# Fenyjelzo.net
KiCad netlist of a schematic drawn in EAGLE
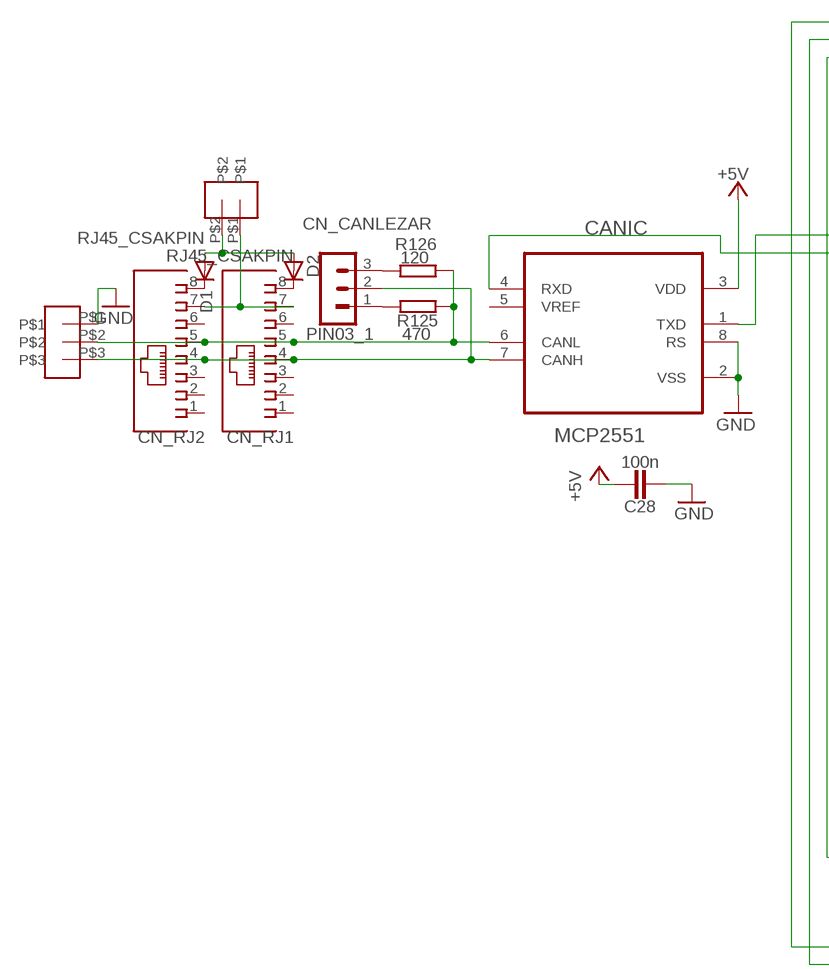
[diagram p0: schematic, sheet 1, part 1 of 2]
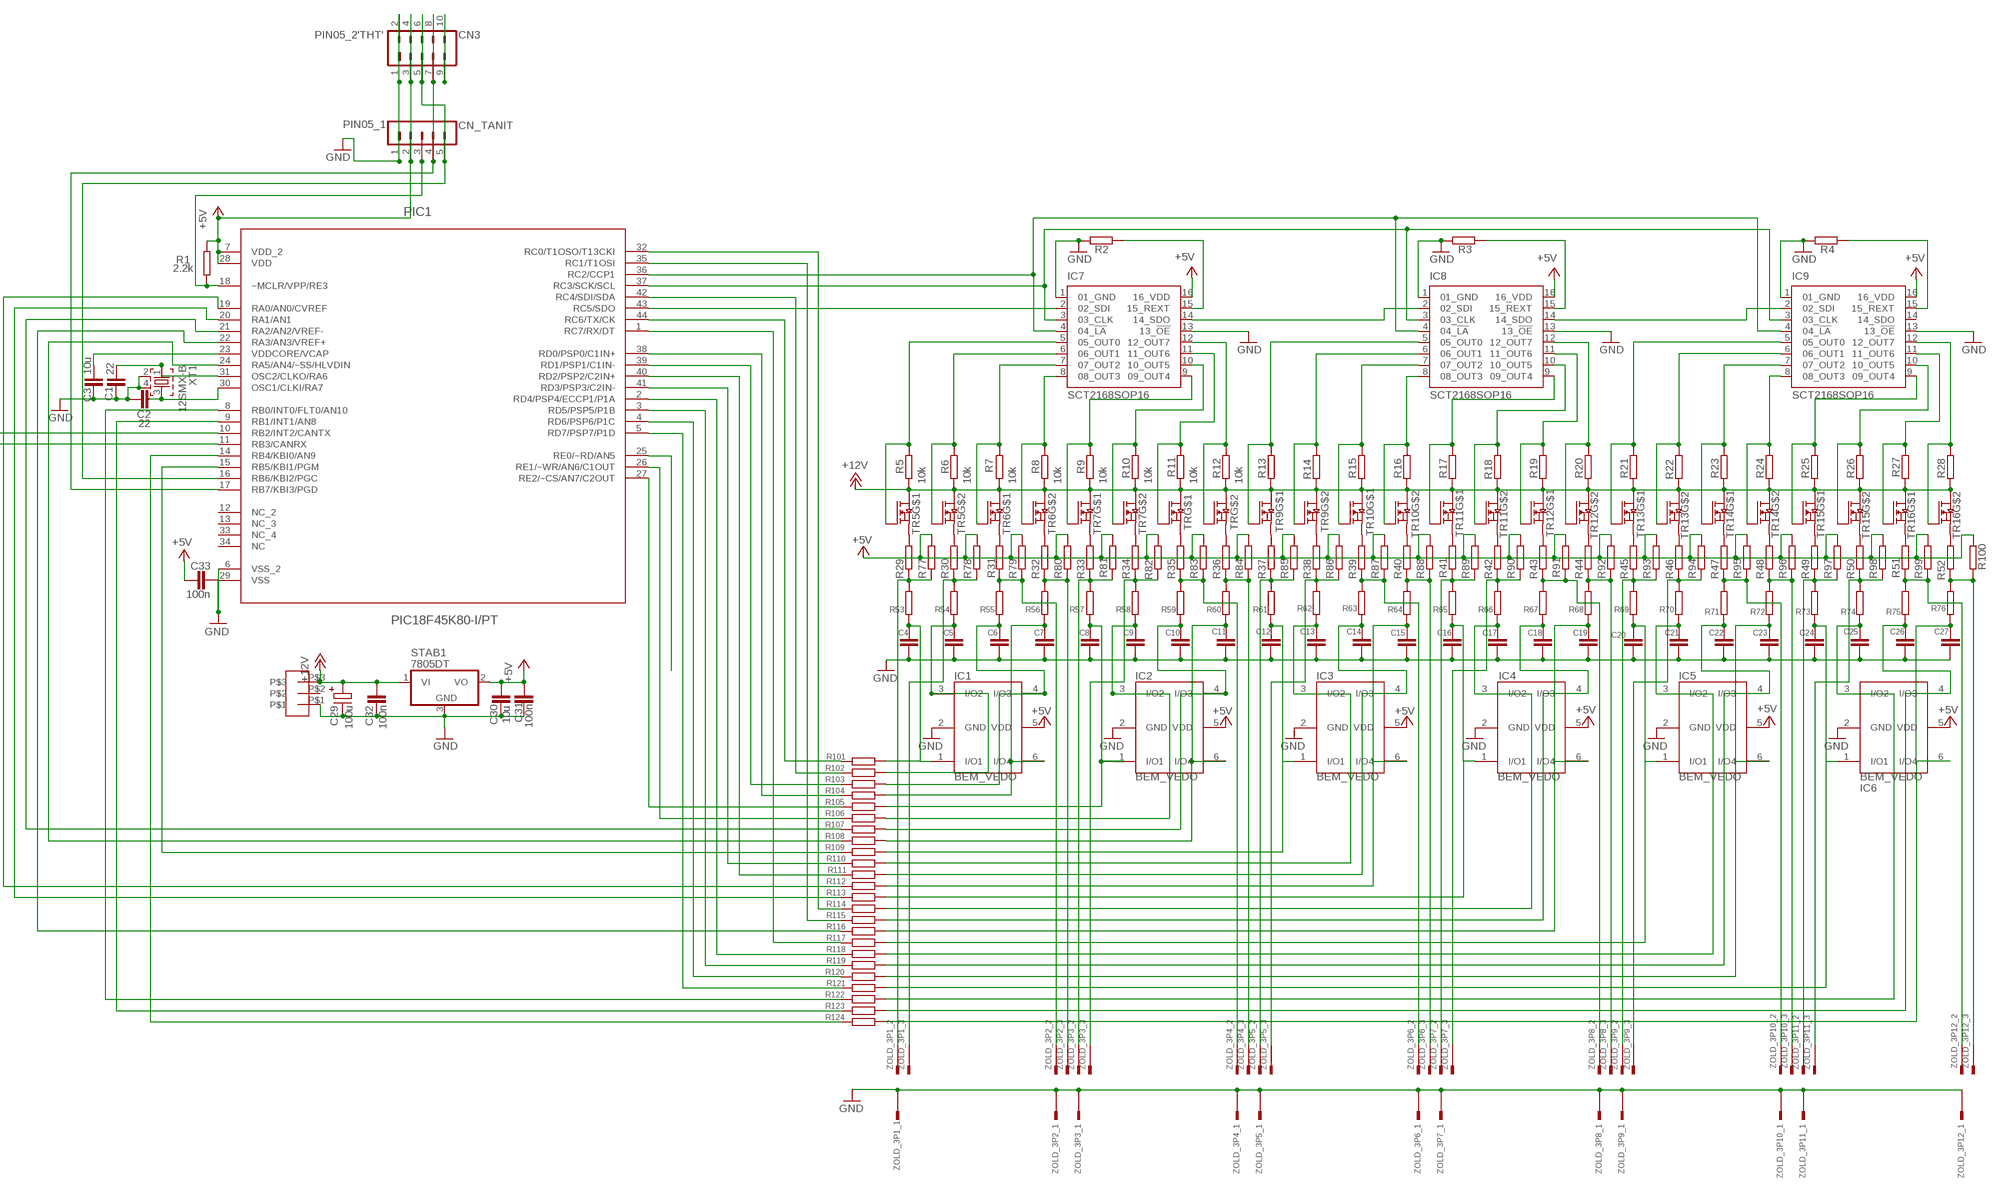
[diagram p1: schematic, sheet 1, part 2 of 2]

(export (version "E")
  (design (tool "Eeschema 10.0.6"))
  (components
    (comp (ref "C1")
      (value "22")
      (footprint "eagle-import:R0805")
      (libsource (lib "eagle-import") (part "C0805"))
    )
    (comp (ref "C2")
      (value "22")
      (footprint "eagle-import:R0805")
      (libsource (lib "eagle-import") (part "C0805"))
    )
    (comp (ref "C3")
      (value "10u")
      (footprint "eagle-import:R0805")
      (libsource (lib "eagle-import") (part "C0805"))
    )
    (comp (ref "C4")
      (value "C0805")
      (footprint "eagle-import:R0805")
      (libsource (lib "eagle-import") (part "C0805"))
    )
    (comp (ref "C5")
      (value "C0805")
      (footprint "eagle-import:R0805")
      (libsource (lib "eagle-import") (part "C0805"))
    )
    (comp (ref "C6")
      (value "C0805")
      (footprint "eagle-import:R0805")
      (libsource (lib "eagle-import") (part "C0805"))
    )
    (comp (ref "C7")
      (value "C0805")
      (footprint "eagle-import:R0805")
      (libsource (lib "eagle-import") (part "C0805"))
    )
    (comp (ref "C8")
      (value "C0805")
      (footprint "eagle-import:R0805")
      (libsource (lib "eagle-import") (part "C0805"))
    )
    (comp (ref "C9")
      (value "C0805")
      (footprint "eagle-import:R0805")
      (libsource (lib "eagle-import") (part "C0805"))
    )
    (comp (ref "C10")
      (value "C0805")
      (footprint "eagle-import:R0805")
      (libsource (lib "eagle-import") (part "C0805"))
    )
    (comp (ref "C11")
      (value "C0805")
      (footprint "eagle-import:R0805")
      (libsource (lib "eagle-import") (part "C0805"))
    )
    (comp (ref "C12")
      (value "C0805")
      (footprint "eagle-import:R0805")
      (libsource (lib "eagle-import") (part "C0805"))
    )
    (comp (ref "C13")
      (value "C0805")
      (footprint "eagle-import:R0805")
      (libsource (lib "eagle-import") (part "C0805"))
    )
    (comp (ref "C14")
      (value "C0805")
      (footprint "eagle-import:R0805")
      (libsource (lib "eagle-import") (part "C0805"))
    )
    (comp (ref "C15")
      (value "C0805")
      (footprint "eagle-import:R0805")
      (libsource (lib "eagle-import") (part "C0805"))
    )
    (comp (ref "C16")
      (value "C0805")
      (footprint "eagle-import:R0805")
      (libsource (lib "eagle-import") (part "C0805"))
    )
    (comp (ref "C17")
      (value "C0805")
      (footprint "eagle-import:R0805")
      (libsource (lib "eagle-import") (part "C0805"))
    )
    (comp (ref "C18")
      (value "C0805")
      (footprint "eagle-import:R0805")
      (libsource (lib "eagle-import") (part "C0805"))
    )
    (comp (ref "C19")
      (value "C0805")
      (footprint "eagle-import:R0805")
      (libsource (lib "eagle-import") (part "C0805"))
    )
    (comp (ref "C20")
      (value "C0805")
      (footprint "eagle-import:R0805")
      (libsource (lib "eagle-import") (part "C0805"))
    )
    (comp (ref "C21")
      (value "C0805")
      (footprint "eagle-import:R0805")
      (libsource (lib "eagle-import") (part "C0805"))
    )
    (comp (ref "C22")
      (value "C0805")
      (footprint "eagle-import:R0805")
      (libsource (lib "eagle-import") (part "C0805"))
    )
    (comp (ref "C23")
      (value "C0805")
      (footprint "eagle-import:R0805")
      (libsource (lib "eagle-import") (part "C0805"))
    )
    (comp (ref "C24")
      (value "C0805")
      (footprint "eagle-import:R0805")
      (libsource (lib "eagle-import") (part "C0805"))
    )
    (comp (ref "C25")
      (value "C0805")
      (footprint "eagle-import:R0805")
      (libsource (lib "eagle-import") (part "C0805"))
    )
    (comp (ref "C26")
      (value "C0805")
      (footprint "eagle-import:R0805")
      (libsource (lib "eagle-import") (part "C0805"))
    )
    (comp (ref "C27")
      (value "C0805")
      (footprint "eagle-import:R0805")
      (libsource (lib "eagle-import") (part "C0805"))
    )
    (comp (ref "C28")
      (value "100n")
      (footprint "eagle-import:R0805")
      (libsource (lib "eagle-import") (part "C0805"))
    )
    (comp (ref "C29")
      (value "100u")
      (footprint "eagle-import:C_EL1RASZT07")
      (libsource (lib "eagle-import") (part "C_EL1R07"))
    )
    (comp (ref "C30")
      (value "10u")
      (footprint "eagle-import:R0805")
      (libsource (lib "eagle-import") (part "C0805"))
    )
    (comp (ref "C31")
      (value "100n")
      (footprint "eagle-import:R0805")
      (libsource (lib "eagle-import") (part "C0805"))
    )
    (comp (ref "C32")
      (value "100n")
      (footprint "eagle-import:R0805")
      (libsource (lib "eagle-import") (part "C0805"))
    )
    (comp (ref "C33")
      (value "100n")
      (footprint "eagle-import:R0805")
      (libsource (lib "eagle-import") (part "C0805"))
    )
    (comp (ref "CANIC")
      (value "MCP2551")
      (footprint "eagle-import:DIP254P762X432-8")
      (fields (field (name "MPN") "MCP2551-I/P"))
      (libsource (lib "eagle-import") (part "MCP2551-I/P"))
    )
    (comp (ref "CN3")
      (value "PIN05_2'THT'")
      (footprint "eagle-import:PIN05_2")
      (libsource (lib "eagle-import") (part "PIN05_2'THT'"))
    )
    (comp (ref "CN_CANLEZAR")
      (value "PIN03_1")
      (footprint "eagle-import:PIN03_1")
      (libsource (lib "eagle-import") (part "PIN03_1"))
    )
    (comp (ref "CN_RJ1")
      (value "RJ45_CSAKPIN")
      (footprint "eagle-import:RJ45_CSAKPIN")
      (libsource (lib "eagle-import") (part "RJ45_CSAKPIN"))
    )
    (comp (ref "CN_RJ2")
      (value "RJ45_CSAKPIN")
      (footprint "eagle-import:RJ45_CSAKPIN")
      (libsource (lib "eagle-import") (part "RJ45_CSAKPIN"))
    )
    (comp (ref "CN_TANIT")
      (value "PIN05_1")
      (footprint "eagle-import:PIN05_1")
      (libsource (lib "eagle-import") (part "PIN05_1"))
    )
    (comp (ref "D1")
      (value "DDO214AC")
      (footprint "eagle-import:DO214AC")
      (libsource (lib "eagle-import") (part "DDO214AC"))
    )
    (comp (ref "D2")
      (value "DDO214AC")
      (footprint "eagle-import:DO214AC")
      (libsource (lib "eagle-import") (part "DDO214AC"))
    )
    (comp (ref "IC1")
      (value "BEM_VEDO")
      (footprint "eagle-import:TSOP-6")
      (libsource (lib "eagle-import") (part "BEM_VEDO"))
    )
    (comp (ref "IC2")
      (value "BEM_VEDO")
      (footprint "eagle-import:TSOP-6")
      (libsource (lib "eagle-import") (part "BEM_VEDO"))
    )
    (comp (ref "IC3")
      (value "BEM_VEDO")
      (footprint "eagle-import:TSOP-6")
      (libsource (lib "eagle-import") (part "BEM_VEDO"))
    )
    (comp (ref "IC4")
      (value "BEM_VEDO")
      (footprint "eagle-import:TSOP-6")
      (libsource (lib "eagle-import") (part "BEM_VEDO"))
    )
    (comp (ref "IC5")
      (value "BEM_VEDO")
      (footprint "eagle-import:TSOP-6")
      (libsource (lib "eagle-import") (part "BEM_VEDO"))
    )
    (comp (ref "IC6")
      (value "BEM_VEDO")
      (footprint "eagle-import:TSOP-6")
      (libsource (lib "eagle-import") (part "BEM_VEDO"))
    )
    (comp (ref "IC7")
      (value "SCT2168SOP16")
      (footprint "eagle-import:SO16")
      (libsource (lib "eagle-import") (part "SCT2168SOP16"))
    )
    (comp (ref "IC8")
      (value "SCT2168SOP16")
      (footprint "eagle-import:SO16")
      (libsource (lib "eagle-import") (part "SCT2168SOP16"))
    )
    (comp (ref "IC9")
      (value "SCT2168SOP16")
      (footprint "eagle-import:SO16")
      (libsource (lib "eagle-import") (part "SCT2168SOP16"))
    )
    (comp (ref "PIC1")
      (value "PIC18F45K80-I/PT")
      (footprint "eagle-import:QFP80P1200X1200X120-44N")
      (fields (field (name "MPN") "PIC18F4580-I/PT"))
      (libsource (lib "eagle-import") (part "PIC18F45K80-I/PT"))
    )
    (comp (ref "R1")
      (value "2.2k")
      (footprint "eagle-import:R0805@1")
      (libsource (lib "eagle-import") (part "R_EU0805"))
    )
    (comp (ref "R2")
      (value "R_EU0805")
      (footprint "eagle-import:R0805@1")
      (libsource (lib "eagle-import") (part "R_EU0805"))
    )
    (comp (ref "R3")
      (value "R_EU0805")
      (footprint "eagle-import:R0805@1")
      (libsource (lib "eagle-import") (part "R_EU0805"))
    )
    (comp (ref "R4")
      (value "R_EU0805")
      (footprint "eagle-import:R0805@1")
      (libsource (lib "eagle-import") (part "R_EU0805"))
    )
    (comp (ref "R5")
      (value "10k")
      (footprint "eagle-import:R0805@1")
      (libsource (lib "eagle-import") (part "R_EU0805"))
    )
    (comp (ref "R6")
      (value "10k")
      (footprint "eagle-import:R0805@1")
      (libsource (lib "eagle-import") (part "R_EU0805"))
    )
    (comp (ref "R7")
      (value "10k")
      (footprint "eagle-import:R0805@1")
      (libsource (lib "eagle-import") (part "R_EU0805"))
    )
    (comp (ref "R8")
      (value "10k")
      (footprint "eagle-import:R0805@1")
      (libsource (lib "eagle-import") (part "R_EU0805"))
    )
    (comp (ref "R9")
      (value "10k")
      (footprint "eagle-import:R0805@1")
      (libsource (lib "eagle-import") (part "R_EU0805"))
    )
    (comp (ref "R10")
      (value "10k")
      (footprint "eagle-import:R0805@1")
      (libsource (lib "eagle-import") (part "R_EU0805"))
    )
    (comp (ref "R11")
      (value "10k")
      (footprint "eagle-import:R0805@1")
      (libsource (lib "eagle-import") (part "R_EU0805"))
    )
    (comp (ref "R12")
      (value "10k")
      (footprint "eagle-import:R0805@1")
      (libsource (lib "eagle-import") (part "R_EU0805"))
    )
    (comp (ref "R13")
      (value "R_EU0805")
      (footprint "eagle-import:R0805@1")
      (libsource (lib "eagle-import") (part "R_EU0805"))
    )
    (comp (ref "R14")
      (value "R_EU0805")
      (footprint "eagle-import:R0805@1")
      (libsource (lib "eagle-import") (part "R_EU0805"))
    )
    (comp (ref "R15")
      (value "R_EU0805")
      (footprint "eagle-import:R0805@1")
      (libsource (lib "eagle-import") (part "R_EU0805"))
    )
    (comp (ref "R16")
      (value "R_EU0805")
      (footprint "eagle-import:R0805@1")
      (libsource (lib "eagle-import") (part "R_EU0805"))
    )
    (comp (ref "R17")
      (value "R_EU0805")
      (footprint "eagle-import:R0805@1")
      (libsource (lib "eagle-import") (part "R_EU0805"))
    )
    (comp (ref "R18")
      (value "R_EU0805")
      (footprint "eagle-import:R0805@1")
      (libsource (lib "eagle-import") (part "R_EU0805"))
    )
    (comp (ref "R19")
      (value "R_EU0805")
      (footprint "eagle-import:R0805@1")
      (libsource (lib "eagle-import") (part "R_EU0805"))
    )
    (comp (ref "R20")
      (value "R_EU0805")
      (footprint "eagle-import:R0805@1")
      (libsource (lib "eagle-import") (part "R_EU0805"))
    )
    (comp (ref "R21")
      (value "R_EU0805")
      (footprint "eagle-import:R0805@1")
      (libsource (lib "eagle-import") (part "R_EU0805"))
    )
    (comp (ref "R22")
      (value "R_EU0805")
      (footprint "eagle-import:R0805@1")
      (libsource (lib "eagle-import") (part "R_EU0805"))
    )
    (comp (ref "R23")
      (value "R_EU0805")
      (footprint "eagle-import:R0805@1")
      (libsource (lib "eagle-import") (part "R_EU0805"))
    )
    (comp (ref "R24")
      (value "R_EU0805")
      (footprint "eagle-import:R0805@1")
      (libsource (lib "eagle-import") (part "R_EU0805"))
    )
    (comp (ref "R25")
      (value "R_EU0805")
      (footprint "eagle-import:R0805@1")
      (libsource (lib "eagle-import") (part "R_EU0805"))
    )
    (comp (ref "R26")
      (value "R_EU0805")
      (footprint "eagle-import:R0805@1")
      (libsource (lib "eagle-import") (part "R_EU0805"))
    )
    (comp (ref "R27")
      (value "R_EU0805")
      (footprint "eagle-import:R0805@1")
      (libsource (lib "eagle-import") (part "R_EU0805"))
    )
    (comp (ref "R28")
      (value "R_EU0805")
      (footprint "eagle-import:R0805@1")
      (libsource (lib "eagle-import") (part "R_EU0805"))
    )
    (comp (ref "R29")
      (value "R_EU0805")
      (footprint "eagle-import:R0805@1")
      (libsource (lib "eagle-import") (part "R_EU0805"))
    )
    (comp (ref "R30")
      (value "R_EU0805")
      (footprint "eagle-import:R0805@1")
      (libsource (lib "eagle-import") (part "R_EU0805"))
    )
    (comp (ref "R31")
      (value "R_EU0805")
      (footprint "eagle-import:R0805@1")
      (libsource (lib "eagle-import") (part "R_EU0805"))
    )
    (comp (ref "R32")
      (value "R_EU0805")
      (footprint "eagle-import:R0805@1")
      (libsource (lib "eagle-import") (part "R_EU0805"))
    )
    (comp (ref "R33")
      (value "R_EU0805")
      (footprint "eagle-import:R0805@1")
      (libsource (lib "eagle-import") (part "R_EU0805"))
    )
    (comp (ref "R34")
      (value "R_EU0805")
      (footprint "eagle-import:R0805@1")
      (libsource (lib "eagle-import") (part "R_EU0805"))
    )
    (comp (ref "R35")
      (value "R_EU0805")
      (footprint "eagle-import:R0805@1")
      (libsource (lib "eagle-import") (part "R_EU0805"))
    )
    (comp (ref "R36")
      (value "R_EU0805")
      (footprint "eagle-import:R0805@1")
      (libsource (lib "eagle-import") (part "R_EU0805"))
    )
    (comp (ref "R37")
      (value "R_EU0805")
      (footprint "eagle-import:R0805@1")
      (libsource (lib "eagle-import") (part "R_EU0805"))
    )
    (comp (ref "R38")
      (value "R_EU0805")
      (footprint "eagle-import:R0805@1")
      (libsource (lib "eagle-import") (part "R_EU0805"))
    )
    (comp (ref "R39")
      (value "R_EU0805")
      (footprint "eagle-import:R0805@1")
      (libsource (lib "eagle-import") (part "R_EU0805"))
    )
    (comp (ref "R40")
      (value "R_EU0805")
      (footprint "eagle-import:R0805@1")
      (libsource (lib "eagle-import") (part "R_EU0805"))
    )
    (comp (ref "R41")
      (value "R_EU0805")
      (footprint "eagle-import:R0805@1")
      (libsource (lib "eagle-import") (part "R_EU0805"))
    )
    (comp (ref "R42")
      (value "R_EU0805")
      (footprint "eagle-import:R0805@1")
      (libsource (lib "eagle-import") (part "R_EU0805"))
    )
    (comp (ref "R43")
      (value "R_EU0805")
      (footprint "eagle-import:R0805@1")
      (libsource (lib "eagle-import") (part "R_EU0805"))
    )
    (comp (ref "R44")
      (value "R_EU0805")
      (footprint "eagle-import:R0805@1")
      (libsource (lib "eagle-import") (part "R_EU0805"))
    )
    (comp (ref "R45")
      (value "R_EU0805")
      (footprint "eagle-import:R0805@1")
      (libsource (lib "eagle-import") (part "R_EU0805"))
    )
    (comp (ref "R46")
      (value "R_EU0805")
      (footprint "eagle-import:R0805@1")
      (libsource (lib "eagle-import") (part "R_EU0805"))
    )
    (comp (ref "R47")
      (value "R_EU0805")
      (footprint "eagle-import:R0805@1")
      (libsource (lib "eagle-import") (part "R_EU0805"))
    )
    (comp (ref "R48")
      (value "R_EU0805")
      (footprint "eagle-import:R0805@1")
      (libsource (lib "eagle-import") (part "R_EU0805"))
    )
    (comp (ref "R49")
      (value "R_EU0805")
      (footprint "eagle-import:R0805@1")
      (libsource (lib "eagle-import") (part "R_EU0805"))
    )
    (comp (ref "R50")
      (value "R_EU0805")
      (footprint "eagle-import:R0805@1")
      (libsource (lib "eagle-import") (part "R_EU0805"))
    )
    (comp (ref "R51")
      (value "R_EU0805")
      (footprint "eagle-import:R0805@1")
      (libsource (lib "eagle-import") (part "R_EU0805"))
    )
    (comp (ref "R52")
      (value "R_EU0805")
      (footprint "eagle-import:R0805@1")
      (libsource (lib "eagle-import") (part "R_EU0805"))
    )
    (comp (ref "R53")
      (value "R_EU0805")
      (footprint "eagle-import:R0805@1")
      (libsource (lib "eagle-import") (part "R_EU0805"))
    )
    (comp (ref "R54")
      (value "R_EU0805")
      (footprint "eagle-import:R0805@1")
      (libsource (lib "eagle-import") (part "R_EU0805"))
    )
    (comp (ref "R55")
      (value "R_EU0805")
      (footprint "eagle-import:R0805@1")
      (libsource (lib "eagle-import") (part "R_EU0805"))
    )
    (comp (ref "R56")
      (value "R_EU0805")
      (footprint "eagle-import:R0805@1")
      (libsource (lib "eagle-import") (part "R_EU0805"))
    )
    (comp (ref "R57")
      (value "R_EU0805")
      (footprint "eagle-import:R0805@1")
      (libsource (lib "eagle-import") (part "R_EU0805"))
    )
    (comp (ref "R58")
      (value "R_EU0805")
      (footprint "eagle-import:R0805@1")
      (libsource (lib "eagle-import") (part "R_EU0805"))
    )
    (comp (ref "R59")
      (value "R_EU0805")
      (footprint "eagle-import:R0805@1")
      (libsource (lib "eagle-import") (part "R_EU0805"))
    )
    (comp (ref "R60")
      (value "R_EU0805")
      (footprint "eagle-import:R0805@1")
      (libsource (lib "eagle-import") (part "R_EU0805"))
    )
    (comp (ref "R61")
      (value "R_EU0805")
      (footprint "eagle-import:R0805@1")
      (libsource (lib "eagle-import") (part "R_EU0805"))
    )
    (comp (ref "R62")
      (value "R_EU0805")
      (footprint "eagle-import:R0805@1")
      (libsource (lib "eagle-import") (part "R_EU0805"))
    )
    (comp (ref "R63")
      (value "R_EU0805")
      (footprint "eagle-import:R0805@1")
      (libsource (lib "eagle-import") (part "R_EU0805"))
    )
    (comp (ref "R64")
      (value "R_EU0805")
      (footprint "eagle-import:R0805@1")
      (libsource (lib "eagle-import") (part "R_EU0805"))
    )
    (comp (ref "R65")
      (value "R_EU0805")
      (footprint "eagle-import:R0805@1")
      (libsource (lib "eagle-import") (part "R_EU0805"))
    )
    (comp (ref "R66")
      (value "R_EU0805")
      (footprint "eagle-import:R0805@1")
      (libsource (lib "eagle-import") (part "R_EU0805"))
    )
    (comp (ref "R67")
      (value "R_EU0805")
      (footprint "eagle-import:R0805@1")
      (libsource (lib "eagle-import") (part "R_EU0805"))
    )
    (comp (ref "R68")
      (value "R_EU0805")
      (footprint "eagle-import:R0805@1")
      (libsource (lib "eagle-import") (part "R_EU0805"))
    )
    (comp (ref "R69")
      (value "R_EU0805")
      (footprint "eagle-import:R0805@1")
      (libsource (lib "eagle-import") (part "R_EU0805"))
    )
    (comp (ref "R70")
      (value "R_EU0805")
      (footprint "eagle-import:R0805@1")
      (libsource (lib "eagle-import") (part "R_EU0805"))
    )
    (comp (ref "R71")
      (value "R_EU0805")
      (footprint "eagle-import:R0805@1")
      (libsource (lib "eagle-import") (part "R_EU0805"))
    )
    (comp (ref "R72")
      (value "R_EU0805")
      (footprint "eagle-import:R0805@1")
      (libsource (lib "eagle-import") (part "R_EU0805"))
    )
    (comp (ref "R73")
      (value "R_EU0805")
      (footprint "eagle-import:R0805@1")
      (libsource (lib "eagle-import") (part "R_EU0805"))
    )
    (comp (ref "R74")
      (value "R_EU0805")
      (footprint "eagle-import:R0805@1")
      (libsource (lib "eagle-import") (part "R_EU0805"))
    )
    (comp (ref "R75")
      (value "R_EU0805")
      (footprint "eagle-import:R0805@1")
      (libsource (lib "eagle-import") (part "R_EU0805"))
    )
    (comp (ref "R76")
      (value "R_EU0805")
      (footprint "eagle-import:R0805@1")
      (libsource (lib "eagle-import") (part "R_EU0805"))
    )
    (comp (ref "R77")
      (value "R_EU0805")
      (footprint "eagle-import:R0805@1")
      (libsource (lib "eagle-import") (part "R_EU0805"))
    )
    (comp (ref "R78")
      (value "R_EU0805")
      (footprint "eagle-import:R0805@1")
      (libsource (lib "eagle-import") (part "R_EU0805"))
    )
    (comp (ref "R79")
      (value "R_EU0805")
      (footprint "eagle-import:R0805@1")
      (libsource (lib "eagle-import") (part "R_EU0805"))
    )
    (comp (ref "R80")
      (value "R_EU0805")
      (footprint "eagle-import:R0805@1")
      (libsource (lib "eagle-import") (part "R_EU0805"))
    )
    (comp (ref "R81")
      (value "R_EU0805")
      (footprint "eagle-import:R0805@1")
      (libsource (lib "eagle-import") (part "R_EU0805"))
    )
    (comp (ref "R82")
      (value "R_EU0805")
      (footprint "eagle-import:R0805@1")
      (libsource (lib "eagle-import") (part "R_EU0805"))
    )
    (comp (ref "R83")
      (value "R_EU0805")
      (footprint "eagle-import:R0805@1")
      (libsource (lib "eagle-import") (part "R_EU0805"))
    )
    (comp (ref "R84")
      (value "R_EU0805")
      (footprint "eagle-import:R0805@1")
      (libsource (lib "eagle-import") (part "R_EU0805"))
    )
    (comp (ref "R85")
      (value "R_EU0805")
      (footprint "eagle-import:R0805@1")
      (libsource (lib "eagle-import") (part "R_EU0805"))
    )
    (comp (ref "R86")
      (value "R_EU0805")
      (footprint "eagle-import:R0805@1")
      (libsource (lib "eagle-import") (part "R_EU0805"))
    )
    (comp (ref "R87")
      (value "R_EU0805")
      (footprint "eagle-import:R0805@1")
      (libsource (lib "eagle-import") (part "R_EU0805"))
    )
    (comp (ref "R88")
      (value "R_EU0805")
      (footprint "eagle-import:R0805@1")
      (libsource (lib "eagle-import") (part "R_EU0805"))
    )
    (comp (ref "R89")
      (value "R_EU0805")
      (footprint "eagle-import:R0805@1")
      (libsource (lib "eagle-import") (part "R_EU0805"))
    )
    (comp (ref "R90")
      (value "R_EU0805")
      (footprint "eagle-import:R0805@1")
      (libsource (lib "eagle-import") (part "R_EU0805"))
    )
    (comp (ref "R91")
      (value "R_EU0805")
      (footprint "eagle-import:R0805@1")
      (libsource (lib "eagle-import") (part "R_EU0805"))
    )
    (comp (ref "R92")
      (value "R_EU0805")
      (footprint "eagle-import:R0805@1")
      (libsource (lib "eagle-import") (part "R_EU0805"))
    )
    (comp (ref "R93")
      (value "R_EU0805")
      (footprint "eagle-import:R0805@1")
      (libsource (lib "eagle-import") (part "R_EU0805"))
    )
    (comp (ref "R94")
      (value "R_EU0805")
      (footprint "eagle-import:R0805@1")
      (libsource (lib "eagle-import") (part "R_EU0805"))
    )
    (comp (ref "R95")
      (value "R_EU0805")
      (footprint "eagle-import:R0805@1")
      (libsource (lib "eagle-import") (part "R_EU0805"))
    )
    (comp (ref "R96")
      (value "R_EU0805")
      (footprint "eagle-import:R0805@1")
      (libsource (lib "eagle-import") (part "R_EU0805"))
    )
    (comp (ref "R97")
      (value "R_EU0805")
      (footprint "eagle-import:R0805@1")
      (libsource (lib "eagle-import") (part "R_EU0805"))
    )
    (comp (ref "R98")
      (value "R_EU0805")
      (footprint "eagle-import:R0805@1")
      (libsource (lib "eagle-import") (part "R_EU0805"))
    )
    (comp (ref "R99")
      (value "R_EU0805")
      (footprint "eagle-import:R0805@1")
      (libsource (lib "eagle-import") (part "R_EU0805"))
    )
    (comp (ref "R100")
      (value "R_EU0805")
      (footprint "eagle-import:R0805@1")
      (libsource (lib "eagle-import") (part "R_EU0805"))
    )
    (comp (ref "R101")
      (value "R_EU0805")
      (footprint "eagle-import:R0805@1")
      (libsource (lib "eagle-import") (part "R_EU0805"))
    )
    (comp (ref "R102")
      (value "R_EU0805")
      (footprint "eagle-import:R0805@1")
      (libsource (lib "eagle-import") (part "R_EU0805"))
    )
    (comp (ref "R103")
      (value "R_EU0805")
      (footprint "eagle-import:R0805@1")
      (libsource (lib "eagle-import") (part "R_EU0805"))
    )
    (comp (ref "R104")
      (value "R_EU0805")
      (footprint "eagle-import:R0805@1")
      (libsource (lib "eagle-import") (part "R_EU0805"))
    )
    (comp (ref "R105")
      (value "R_EU0805")
      (footprint "eagle-import:R0805@1")
      (libsource (lib "eagle-import") (part "R_EU0805"))
    )
    (comp (ref "R106")
      (value "R_EU0805")
      (footprint "eagle-import:R0805@1")
      (libsource (lib "eagle-import") (part "R_EU0805"))
    )
    (comp (ref "R107")
      (value "R_EU0805")
      (footprint "eagle-import:R0805@1")
      (libsource (lib "eagle-import") (part "R_EU0805"))
    )
    (comp (ref "R108")
      (value "R_EU0805")
      (footprint "eagle-import:R0805@1")
      (libsource (lib "eagle-import") (part "R_EU0805"))
    )
    (comp (ref "R109")
      (value "R_EU0805")
      (footprint "eagle-import:R0805@1")
      (libsource (lib "eagle-import") (part "R_EU0805"))
    )
    (comp (ref "R110")
      (value "R_EU0805")
      (footprint "eagle-import:R0805@1")
      (libsource (lib "eagle-import") (part "R_EU0805"))
    )
    (comp (ref "R111")
      (value "R_EU0805")
      (footprint "eagle-import:R0805@1")
      (libsource (lib "eagle-import") (part "R_EU0805"))
    )
    (comp (ref "R112")
      (value "R_EU0805")
      (footprint "eagle-import:R0805@1")
      (libsource (lib "eagle-import") (part "R_EU0805"))
    )
    (comp (ref "R113")
      (value "R_EU0805")
      (footprint "eagle-import:R0805@1")
      (libsource (lib "eagle-import") (part "R_EU0805"))
    )
    (comp (ref "R114")
      (value "R_EU0805")
      (footprint "eagle-import:R0805@1")
      (libsource (lib "eagle-import") (part "R_EU0805"))
    )
    (comp (ref "R115")
      (value "R_EU0805")
      (footprint "eagle-import:R0805@1")
      (libsource (lib "eagle-import") (part "R_EU0805"))
    )
    (comp (ref "R116")
      (value "R_EU0805")
      (footprint "eagle-import:R0805@1")
      (libsource (lib "eagle-import") (part "R_EU0805"))
    )
    (comp (ref "R117")
      (value "R_EU0805")
      (footprint "eagle-import:R0805@1")
      (libsource (lib "eagle-import") (part "R_EU0805"))
    )
    (comp (ref "R118")
      (value "R_EU0805")
      (footprint "eagle-import:R0805@1")
      (libsource (lib "eagle-import") (part "R_EU0805"))
    )
    (comp (ref "R119")
      (value "R_EU0805")
      (footprint "eagle-import:R0805@1")
      (libsource (lib "eagle-import") (part "R_EU0805"))
    )
    (comp (ref "R120")
      (value "R_EU0805")
      (footprint "eagle-import:R0805@1")
      (libsource (lib "eagle-import") (part "R_EU0805"))
    )
    (comp (ref "R121")
      (value "R_EU0805")
      (footprint "eagle-import:R0805@1")
      (libsource (lib "eagle-import") (part "R_EU0805"))
    )
    (comp (ref "R122")
      (value "R_EU0805")
      (footprint "eagle-import:R0805@1")
      (libsource (lib "eagle-import") (part "R_EU0805"))
    )
    (comp (ref "R123")
      (value "R_EU0805")
      (footprint "eagle-import:R0805@1")
      (libsource (lib "eagle-import") (part "R_EU0805"))
    )
    (comp (ref "R124")
      (value "R_EU0805")
      (footprint "eagle-import:R0805@1")
      (libsource (lib "eagle-import") (part "R_EU0805"))
    )
    (comp (ref "R125")
      (value "470")
      (footprint "eagle-import:R0805@1")
      (libsource (lib "eagle-import") (part "R_EU0805"))
    )
    (comp (ref "R126")
      (value "120")
      (footprint "eagle-import:R0805@1")
      (libsource (lib "eagle-import") (part "R_EU0805"))
    )
    (comp (ref "STAB1")
      (value "7805DT")
      (footprint "eagle-import:TO252")
      (libsource (lib "eagle-import") (part "78DT05"))
    )
    (comp (ref "TR")
      (value "AP2625GY-HF-3SOT26")
      (footprint "eagle-import:SOT26")
      (libsource (lib "eagle-import") (part "AP2625GY-HF-3SOT26"))
    )
    (comp (ref "TR5")
      (value "AP2625GY-HF-3SOT26")
      (footprint "eagle-import:SOT26")
      (libsource (lib "eagle-import") (part "AP2625GY-HF-3SOT26"))
    )
    (comp (ref "TR6")
      (value "AP2625GY-HF-3SOT26")
      (footprint "eagle-import:SOT26")
      (libsource (lib "eagle-import") (part "AP2625GY-HF-3SOT26"))
    )
    (comp (ref "TR7")
      (value "AP2625GY-HF-3SOT26")
      (footprint "eagle-import:SOT26")
      (libsource (lib "eagle-import") (part "AP2625GY-HF-3SOT26"))
    )
    (comp (ref "TR9")
      (value "AP2625GY-HF-3SOT26")
      (footprint "eagle-import:SOT26")
      (libsource (lib "eagle-import") (part "AP2625GY-HF-3SOT26"))
    )
    (comp (ref "TR10")
      (value "AP2625GY-HF-3SOT26")
      (footprint "eagle-import:SOT26")
      (libsource (lib "eagle-import") (part "AP2625GY-HF-3SOT26"))
    )
    (comp (ref "TR11")
      (value "AP2625GY-HF-3SOT26")
      (footprint "eagle-import:SOT26")
      (libsource (lib "eagle-import") (part "AP2625GY-HF-3SOT26"))
    )
    (comp (ref "TR12")
      (value "AP2625GY-HF-3SOT26")
      (footprint "eagle-import:SOT26")
      (libsource (lib "eagle-import") (part "AP2625GY-HF-3SOT26"))
    )
    (comp (ref "TR13")
      (value "AP2625GY-HF-3SOT26")
      (footprint "eagle-import:SOT26")
      (libsource (lib "eagle-import") (part "AP2625GY-HF-3SOT26"))
    )
    (comp (ref "TR14")
      (value "AP2625GY-HF-3SOT26")
      (footprint "eagle-import:SOT26")
      (libsource (lib "eagle-import") (part "AP2625GY-HF-3SOT26"))
    )
    (comp (ref "TR15")
      (value "AP2625GY-HF-3SOT26")
      (footprint "eagle-import:SOT26")
      (libsource (lib "eagle-import") (part "AP2625GY-HF-3SOT26"))
    )
    (comp (ref "TR16")
      (value "AP2625GY-HF-3SOT26")
      (footprint "eagle-import:SOT26")
      (libsource (lib "eagle-import") (part "AP2625GY-HF-3SOT26"))
    )
    (comp (ref "U$1")
      (value "FEHER_TUS_3")
      (footprint "eagle-import:FEHER_TUS_3")
      (libsource (lib "eagle-import") (part "FEHER_TUS_3"))
    )
    (comp (ref "U$20")
      (value "FEHER_TUS_3")
      (footprint "eagle-import:FEHER_TUS_3")
      (libsource (lib "eagle-import") (part "FEHER_TUS_3"))
    )
    (comp (ref "U$21")
      (value "FEHER_TUS_2ALLO")
      (footprint "eagle-import:FEHER_TUS_2")
      (libsource (lib "eagle-import") (part "FEHER_TUS_2ALLO"))
    )
    (comp (ref "XT1")
      (value "12SMX-B")
      (footprint "eagle-import:12SMX-B")
      (libsource (lib "eagle-import") (part "12SMX-B"))
    )
    (comp (ref "ZOLD_3P1")
      (value "ZOLD_KICSI_3P")
      (footprint "eagle-import:ZOLD_KICSI_3P")
      (libsource (lib "eagle-import") (part "ZOLD_KICSI_3P"))
    )
    (comp (ref "ZOLD_3P2")
      (value "ZOLD_KICSI_3P")
      (footprint "eagle-import:ZOLD_KICSI_3P")
      (libsource (lib "eagle-import") (part "ZOLD_KICSI_3P"))
    )
    (comp (ref "ZOLD_3P3")
      (value "ZOLD_KICSI_3P")
      (footprint "eagle-import:ZOLD_KICSI_3P")
      (libsource (lib "eagle-import") (part "ZOLD_KICSI_3P"))
    )
    (comp (ref "ZOLD_3P4")
      (value "ZOLD_KICSI_3P")
      (footprint "eagle-import:ZOLD_KICSI_3P")
      (libsource (lib "eagle-import") (part "ZOLD_KICSI_3P"))
    )
    (comp (ref "ZOLD_3P5")
      (value "ZOLD_KICSI_3P")
      (footprint "eagle-import:ZOLD_KICSI_3P")
      (libsource (lib "eagle-import") (part "ZOLD_KICSI_3P"))
    )
    (comp (ref "ZOLD_3P6")
      (value "ZOLD_KICSI_3P")
      (footprint "eagle-import:ZOLD_KICSI_3P")
      (libsource (lib "eagle-import") (part "ZOLD_KICSI_3P"))
    )
    (comp (ref "ZOLD_3P7")
      (value "ZOLD_KICSI_3P")
      (footprint "eagle-import:ZOLD_KICSI_3P")
      (libsource (lib "eagle-import") (part "ZOLD_KICSI_3P"))
    )
    (comp (ref "ZOLD_3P8")
      (value "ZOLD_KICSI_3P")
      (footprint "eagle-import:ZOLD_KICSI_3P")
      (libsource (lib "eagle-import") (part "ZOLD_KICSI_3P"))
    )
    (comp (ref "ZOLD_3P9")
      (value "ZOLD_KICSI_3P")
      (footprint "eagle-import:ZOLD_KICSI_3P")
      (libsource (lib "eagle-import") (part "ZOLD_KICSI_3P"))
    )
    (comp (ref "ZOLD_3P10")
      (value "ZOLD_KICSI_3P")
      (footprint "eagle-import:ZOLD_KICSI_3P")
      (libsource (lib "eagle-import") (part "ZOLD_KICSI_3P"))
    )
    (comp (ref "ZOLD_3P11")
      (value "ZOLD_KICSI_3P")
      (footprint "eagle-import:ZOLD_KICSI_3P")
      (libsource (lib "eagle-import") (part "ZOLD_KICSI_3P"))
    )
    (comp (ref "ZOLD_3P12")
      (value "ZOLD_KICSI_3P")
      (footprint "eagle-import:ZOLD_KICSI_3P")
      (libsource (lib "eagle-import") (part "ZOLD_KICSI_3P"))
    )
  )
  (nets
    (net (code "1") (name "+5V") (class "Default")
      (node (ref "C28") (pin "1") (pinfunction "1_1") (pintype "passive"))
      (node (ref "C30") (pin "1") (pinfunction "1_1") (pintype "passive"))
      (node (ref "C31") (pin "1") (pinfunction "1_1") (pintype "passive"))
      (node (ref "C33") (pin "2") (pinfunction "2_2") (pintype "passive"))
      (node (ref "CANIC") (pin "3") (pinfunction "VDD_3") (pintype "power_in"))
      (node (ref "CN3") (pin "3") (pinfunction "3_3") (pintype "passive"))
      (node (ref "CN3") (pin "4") (pinfunction "4_4") (pintype "passive"))
      (node (ref "CN_TANIT") (pin "2") (pinfunction "2_2") (pintype "passive"))
      (node (ref "IC1") (pin "5") (pinfunction "VDD_5") (pintype "bidirectional"))
      (node (ref "IC2") (pin "5") (pinfunction "VDD_5") (pintype "bidirectional"))
      (node (ref "IC3") (pin "5") (pinfunction "VDD_5") (pintype "bidirectional"))
      (node (ref "IC4") (pin "5") (pinfunction "VDD_5") (pintype "bidirectional"))
      (node (ref "IC5") (pin "5") (pinfunction "VDD_5") (pintype "bidirectional"))
      (node (ref "IC6") (pin "5") (pinfunction "VDD_5") (pintype "bidirectional"))
      (node (ref "IC7") (pin "16") (pinfunction "16_VDD_16") (pintype "power_in"))
      (node (ref "IC8") (pin "16") (pinfunction "16_VDD_16") (pintype "power_in"))
      (node (ref "IC9") (pin "16") (pinfunction "16_VDD_16") (pintype "power_in"))
      (node (ref "PIC1") (pin "28") (pinfunction "VDD_28") (pintype "power_in"))
      (node (ref "PIC1") (pin "7") (pinfunction "VDD_2_7") (pintype "power_in"))
      (node (ref "R1") (pin "2") (pinfunction "E_2") (pintype "passive"))
      (node (ref "R100") (pin "1") (pinfunction "A_1") (pintype "passive"))
      (node (ref "R77") (pin "1") (pinfunction "A_1") (pintype "passive"))
      (node (ref "R78") (pin "1") (pinfunction "A_1") (pintype "passive"))
      (node (ref "R79") (pin "1") (pinfunction "A_1") (pintype "passive"))
      (node (ref "R80") (pin "1") (pinfunction "A_1") (pintype "passive"))
      (node (ref "R81") (pin "1") (pinfunction "A_1") (pintype "passive"))
      (node (ref "R82") (pin "1") (pinfunction "A_1") (pintype "passive"))
      (node (ref "R83") (pin "1") (pinfunction "A_1") (pintype "passive"))
      (node (ref "R84") (pin "1") (pinfunction "A_1") (pintype "passive"))
      (node (ref "R85") (pin "1") (pinfunction "A_1") (pintype "passive"))
      (node (ref "R86") (pin "1") (pinfunction "A_1") (pintype "passive"))
      (node (ref "R87") (pin "1") (pinfunction "A_1") (pintype "passive"))
      (node (ref "R88") (pin "1") (pinfunction "A_1") (pintype "passive"))
      (node (ref "R89") (pin "1") (pinfunction "A_1") (pintype "passive"))
      (node (ref "R90") (pin "1") (pinfunction "A_1") (pintype "passive"))
      (node (ref "R91") (pin "1") (pinfunction "A_1") (pintype "passive"))
      (node (ref "R92") (pin "1") (pinfunction "A_1") (pintype "passive"))
      (node (ref "R93") (pin "1") (pinfunction "A_1") (pintype "passive"))
      (node (ref "R94") (pin "1") (pinfunction "A_1") (pintype "passive"))
      (node (ref "R95") (pin "1") (pinfunction "A_1") (pintype "passive"))
      (node (ref "R96") (pin "1") (pinfunction "A_1") (pintype "passive"))
      (node (ref "R97") (pin "1") (pinfunction "A_1") (pintype "passive"))
      (node (ref "R98") (pin "1") (pinfunction "A_1") (pintype "passive"))
      (node (ref "R99") (pin "1") (pinfunction "A_1") (pintype "passive"))
      (node (ref "STAB1") (pin "2") (pinfunction "VO_2") (pintype "passive"))
    )
    (net (code "2") (name "+12V") (class "Default")
      (node (ref "C29") (pin "P+") (pinfunction "P+_P+") (pintype "passive"))
      (node (ref "C32") (pin "1") (pinfunction "1_1") (pintype "passive"))
      (node (ref "R10") (pin "1") (pinfunction "A_1") (pintype "passive"))
      (node (ref "R11") (pin "1") (pinfunction "A_1") (pintype "passive"))
      (node (ref "R12") (pin "1") (pinfunction "A_1") (pintype "passive"))
      (node (ref "R13") (pin "1") (pinfunction "A_1") (pintype "passive"))
      (node (ref "R14") (pin "1") (pinfunction "A_1") (pintype "passive"))
      (node (ref "R15") (pin "1") (pinfunction "A_1") (pintype "passive"))
      (node (ref "R16") (pin "1") (pinfunction "A_1") (pintype "passive"))
      (node (ref "R17") (pin "1") (pinfunction "A_1") (pintype "passive"))
      (node (ref "R18") (pin "1") (pinfunction "A_1") (pintype "passive"))
      (node (ref "R19") (pin "1") (pinfunction "A_1") (pintype "passive"))
      (node (ref "R20") (pin "1") (pinfunction "A_1") (pintype "passive"))
      (node (ref "R21") (pin "1") (pinfunction "A_1") (pintype "passive"))
      (node (ref "R22") (pin "1") (pinfunction "A_1") (pintype "passive"))
      (node (ref "R23") (pin "1") (pinfunction "A_1") (pintype "passive"))
      (node (ref "R24") (pin "1") (pinfunction "A_1") (pintype "passive"))
      (node (ref "R25") (pin "1") (pinfunction "A_1") (pintype "passive"))
      (node (ref "R26") (pin "1") (pinfunction "A_1") (pintype "passive"))
      (node (ref "R27") (pin "1") (pinfunction "A_1") (pintype "passive"))
      (node (ref "R28") (pin "1") (pinfunction "A_1") (pintype "passive"))
      (node (ref "R5") (pin "1") (pinfunction "A_1") (pintype "passive"))
      (node (ref "R6") (pin "1") (pinfunction "A_1") (pintype "passive"))
      (node (ref "R7") (pin "1") (pinfunction "A_1") (pintype "passive"))
      (node (ref "R8") (pin "1") (pinfunction "A_1") (pintype "passive"))
      (node (ref "R9") (pin "1") (pinfunction "A_1") (pintype "passive"))
      (node (ref "STAB1") (pin "1") (pinfunction "VI_1") (pintype "input"))
      (node (ref "TR") (pin "P$4") (pinfunction "D_P$4") (pintype "passive"))
      (node (ref "TR") (pin "P$6") (pinfunction "D_P$6") (pintype "passive"))
      (node (ref "TR10") (pin "P$4") (pinfunction "D_P$4") (pintype "passive"))
      (node (ref "TR10") (pin "P$6") (pinfunction "D_P$6") (pintype "passive"))
      (node (ref "TR11") (pin "P$4") (pinfunction "D_P$4") (pintype "passive"))
      (node (ref "TR11") (pin "P$6") (pinfunction "D_P$6") (pintype "passive"))
      (node (ref "TR12") (pin "P$4") (pinfunction "D_P$4") (pintype "passive"))
      (node (ref "TR12") (pin "P$6") (pinfunction "D_P$6") (pintype "passive"))
      (node (ref "TR13") (pin "P$4") (pinfunction "D_P$4") (pintype "passive"))
      (node (ref "TR13") (pin "P$6") (pinfunction "D_P$6") (pintype "passive"))
      (node (ref "TR14") (pin "P$4") (pinfunction "D_P$4") (pintype "passive"))
      (node (ref "TR14") (pin "P$6") (pinfunction "D_P$6") (pintype "passive"))
      (node (ref "TR15") (pin "P$4") (pinfunction "D_P$4") (pintype "passive"))
      (node (ref "TR15") (pin "P$6") (pinfunction "D_P$6") (pintype "passive"))
      (node (ref "TR16") (pin "P$4") (pinfunction "D_P$4") (pintype "passive"))
      (node (ref "TR16") (pin "P$6") (pinfunction "D_P$6") (pintype "passive"))
      (node (ref "TR5") (pin "P$4") (pinfunction "D_P$4") (pintype "passive"))
      (node (ref "TR5") (pin "P$6") (pinfunction "D_P$6") (pintype "passive"))
      (node (ref "TR6") (pin "P$4") (pinfunction "D_P$4") (pintype "passive"))
      (node (ref "TR6") (pin "P$6") (pinfunction "D_P$6") (pintype "passive"))
      (node (ref "TR7") (pin "P$4") (pinfunction "D_P$4") (pintype "passive"))
      (node (ref "TR7") (pin "P$6") (pinfunction "D_P$6") (pintype "passive"))
      (node (ref "TR9") (pin "P$4") (pinfunction "D_P$4") (pintype "passive"))
      (node (ref "TR9") (pin "P$6") (pinfunction "D_P$6") (pintype "passive"))
      (node (ref "U$20") (pin "P$3") (pinfunction "P$3_P$3") (pintype "bidirectional"))
    )
    (net (code "3") (name "GND") (class "Default")
      (node (ref "C1") (pin "2") (pinfunction "2_2") (pintype "passive"))
      (node (ref "C10") (pin "2") (pinfunction "2_2") (pintype "passive"))
      (node (ref "C11") (pin "2") (pinfunction "2_2") (pintype "passive"))
      (node (ref "C12") (pin "2") (pinfunction "2_2") (pintype "passive"))
      (node (ref "C13") (pin "2") (pinfunction "2_2") (pintype "passive"))
      (node (ref "C14") (pin "2") (pinfunction "2_2") (pintype "passive"))
      (node (ref "C15") (pin "2") (pinfunction "2_2") (pintype "passive"))
      (node (ref "C16") (pin "2") (pinfunction "2_2") (pintype "passive"))
      (node (ref "C17") (pin "2") (pinfunction "2_2") (pintype "passive"))
      (node (ref "C18") (pin "2") (pinfunction "2_2") (pintype "passive"))
      (node (ref "C19") (pin "2") (pinfunction "2_2") (pintype "passive"))
      (node (ref "C2") (pin "2") (pinfunction "2_2") (pintype "passive"))
      (node (ref "C20") (pin "2") (pinfunction "2_2") (pintype "passive"))
      (node (ref "C21") (pin "2") (pinfunction "2_2") (pintype "passive"))
      (node (ref "C22") (pin "2") (pinfunction "2_2") (pintype "passive"))
      (node (ref "C23") (pin "2") (pinfunction "2_2") (pintype "passive"))
      (node (ref "C24") (pin "2") (pinfunction "2_2") (pintype "passive"))
      (node (ref "C25") (pin "2") (pinfunction "2_2") (pintype "passive"))
      (node (ref "C26") (pin "2") (pinfunction "2_2") (pintype "passive"))
      (node (ref "C27") (pin "2") (pinfunction "2_2") (pintype "passive"))
      (node (ref "C28") (pin "2") (pinfunction "2_2") (pintype "passive"))
      (node (ref "C29") (pin "P-") (pinfunction "P-_P-") (pintype "passive"))
      (node (ref "C3") (pin "2") (pinfunction "2_2") (pintype "passive"))
      (node (ref "C30") (pin "2") (pinfunction "2_2") (pintype "passive"))
      (node (ref "C31") (pin "2") (pinfunction "2_2") (pintype "passive"))
      (node (ref "C32") (pin "2") (pinfunction "2_2") (pintype "passive"))
      (node (ref "C33") (pin "1") (pinfunction "1_1") (pintype "passive"))
      (node (ref "C4") (pin "2") (pinfunction "2_2") (pintype "passive"))
      (node (ref "C5") (pin "2") (pinfunction "2_2") (pintype "passive"))
      (node (ref "C6") (pin "2") (pinfunction "2_2") (pintype "passive"))
      (node (ref "C7") (pin "2") (pinfunction "2_2") (pintype "passive"))
      (node (ref "C8") (pin "2") (pinfunction "2_2") (pintype "passive"))
      (node (ref "C9") (pin "2") (pinfunction "2_2") (pintype "passive"))
      (node (ref "CANIC") (pin "2") (pinfunction "VSS_2") (pintype "power_in"))
      (node (ref "CANIC") (pin "8") (pinfunction "RS_8") (pintype "input"))
      (node (ref "CN3") (pin "1") (pinfunction "1_1") (pintype "passive"))
      (node (ref "CN3") (pin "2") (pinfunction "2_2") (pintype "passive"))
      (node (ref "CN_TANIT") (pin "1") (pinfunction "1_1") (pintype "passive"))
      (node (ref "IC1") (pin "2") (pinfunction "GND_2") (pintype "bidirectional"))
      (node (ref "IC2") (pin "2") (pinfunction "GND_2") (pintype "bidirectional"))
      (node (ref "IC3") (pin "2") (pinfunction "GND_2") (pintype "bidirectional"))
      (node (ref "IC4") (pin "2") (pinfunction "GND_2") (pintype "bidirectional"))
      (node (ref "IC5") (pin "2") (pinfunction "GND_2") (pintype "bidirectional"))
      (node (ref "IC6") (pin "2") (pinfunction "GND_2") (pintype "bidirectional"))
      (node (ref "IC7") (pin "1") (pinfunction "01_GND_1") (pintype "power_in"))
      (node (ref "IC7") (pin "13") (pinfunction "13_~{OE}_13") (pintype "input"))
      (node (ref "IC8") (pin "1") (pinfunction "01_GND_1") (pintype "power_in"))
      (node (ref "IC8") (pin "13") (pinfunction "13_~{OE}_13") (pintype "input"))
      (node (ref "IC9") (pin "1") (pinfunction "01_GND_1") (pintype "power_in"))
      (node (ref "IC9") (pin "13") (pinfunction "13_~{OE}_13") (pintype "input"))
      (node (ref "PIC1") (pin "29") (pinfunction "VSS_29") (pintype "power_in"))
      (node (ref "PIC1") (pin "6") (pinfunction "VSS_2_6") (pintype "power_in"))
      (node (ref "R2") (pin "1") (pinfunction "A_1") (pintype "passive"))
      (node (ref "R3") (pin "1") (pinfunction "A_1") (pintype "passive"))
      (node (ref "R4") (pin "1") (pinfunction "A_1") (pintype "passive"))
      (node (ref "STAB1") (pin "3") (pinfunction "GND_3") (pintype "passive"))
      (node (ref "U$1") (pin "P$1") (pinfunction "P$1_P$1") (pintype "bidirectional"))
      (node (ref "U$20") (pin "P$1") (pinfunction "P$1_P$1") (pintype "bidirectional"))
      (node (ref "XT1") (pin "2") (pinfunction "2_2") (pintype "passive"))
      (node (ref "XT1") (pin "4") (pinfunction "4_4") (pintype "passive"))
      (node (ref "ZOLD_3P1") (pin "1") (pinfunction "1_1") (pintype "passive"))
      (node (ref "ZOLD_3P10") (pin "1") (pinfunction "1_1") (pintype "passive"))
      (node (ref "ZOLD_3P11") (pin "1") (pinfunction "1_1") (pintype "passive"))
      (node (ref "ZOLD_3P12") (pin "1") (pinfunction "1_1") (pintype "passive"))
      (node (ref "ZOLD_3P2") (pin "1") (pinfunction "1_1") (pintype "passive"))
      (node (ref "ZOLD_3P3") (pin "1") (pinfunction "1_1") (pintype "passive"))
      (node (ref "ZOLD_3P4") (pin "1") (pinfunction "1_1") (pintype "passive"))
      (node (ref "ZOLD_3P5") (pin "1") (pinfunction "1_1") (pintype "passive"))
      (node (ref "ZOLD_3P6") (pin "1") (pinfunction "1_1") (pintype "passive"))
      (node (ref "ZOLD_3P7") (pin "1") (pinfunction "1_1") (pintype "passive"))
      (node (ref "ZOLD_3P8") (pin "1") (pinfunction "1_1") (pintype "passive"))
      (node (ref "ZOLD_3P9") (pin "1") (pinfunction "1_1") (pintype "passive"))
    )
    (net (code "4") (name "Net-(CANIC-CANH)") (class "Default")
      (node (ref "CANIC") (pin "7") (pinfunction "CANH_7") (pintype "bidirectional"))
      (node (ref "CN_CANLEZAR") (pin "2") (pinfunction "2_2") (pintype "passive"))
      (node (ref "CN_RJ1") (pin "4") (pinfunction "4_4") (pintype "passive"))
      (node (ref "CN_RJ2") (pin "4") (pinfunction "4_4") (pintype "passive"))
      (node (ref "U$1") (pin "P$3") (pinfunction "P$3_P$3") (pintype "bidirectional"))
    )
    (net (code "5") (name "Net-(CANIC-CANL)") (class "Default")
      (node (ref "CANIC") (pin "6") (pinfunction "CANL_6") (pintype "bidirectional"))
      (node (ref "CN_RJ1") (pin "5") (pinfunction "5_5") (pintype "passive"))
      (node (ref "CN_RJ2") (pin "5") (pinfunction "5_5") (pintype "passive"))
      (node (ref "R125") (pin "1") (pinfunction "A_1") (pintype "passive"))
      (node (ref "R126") (pin "2") (pinfunction "E_2") (pintype "passive"))
      (node (ref "U$1") (pin "P$2") (pinfunction "P$2_P$2") (pintype "bidirectional"))
    )
    (net (code "6") (name "Net-(CANIC-RXD)") (class "Default")
      (node (ref "CANIC") (pin "4") (pinfunction "RXD_4") (pintype "output"))
      (node (ref "PIC1") (pin "11") (pinfunction "RB3/CANRX_11") (pintype "bidirectional"))
    )
    (net (code "7") (name "Net-(CANIC-TXD)") (class "Default")
      (node (ref "CANIC") (pin "1") (pinfunction "TXD_1") (pintype "input"))
      (node (ref "PIC1") (pin "10") (pinfunction "RB2/INT2/CANTX_10") (pintype "bidirectional"))
    )
    (net (code "8") (name "Net-(CN3-Pad10)") (class "Default")
      (node (ref "CN3") (pin "10") (pinfunction "10_10") (pintype "passive"))
      (node (ref "CN3") (pin "9") (pinfunction "9_9") (pintype "passive"))
    )
    (net (code "9") (name "Net-(CN_RJ1-Pad7)") (class "Default")
      (node (ref "CN_RJ1") (pin "7") (pinfunction "7_7") (pintype "passive"))
      (node (ref "CN_RJ2") (pin "7") (pinfunction "7_7") (pintype "passive"))
      (node (ref "U$21") (pin "P$1") (pinfunction "P$1_P$1") (pintype "bidirectional"))
    )
    (net (code "10") (name "Net-(CN_RJ1-Pad8)") (class "Default")
      (node (ref "CN_RJ1") (pin "8") (pinfunction "8_8") (pintype "passive"))
      (node (ref "D2") (pin "C") (pinfunction "C_C") (pintype "passive"))
    )
    (net (code "11") (name "Net-(CN_RJ2-Pad8)") (class "Default")
      (node (ref "CN_RJ2") (pin "8") (pinfunction "8_8") (pintype "passive"))
      (node (ref "D1") (pin "C") (pinfunction "C_C") (pintype "passive"))
    )
    (net (code "12") (name "Net-(D1-PadA)") (class "Default")
      (node (ref "D1") (pin "A") (pinfunction "A_A") (pintype "passive"))
      (node (ref "D2") (pin "A") (pinfunction "A_A") (pintype "passive"))
      (node (ref "U$21") (pin "P$2") (pinfunction "P$2_P$2") (pintype "bidirectional"))
    )
    (net (code "13") (name "Net-(IC1-I{slash}O1)") (class "Default")
      (node (ref "C4") (pin "1") (pinfunction "1_1") (pintype "passive"))
      (node (ref "IC1") (pin "1") (pinfunction "I/O1_1") (pintype "bidirectional"))
      (node (ref "R101") (pin "2") (pinfunction "E_2") (pintype "passive"))
      (node (ref "R53") (pin "1") (pinfunction "A_1") (pintype "passive"))
    )
    (net (code "14") (name "Net-(IC1-I{slash}O2)") (class "Default")
      (node (ref "C5") (pin "1") (pinfunction "1_1") (pintype "passive"))
      (node (ref "IC1") (pin "3") (pinfunction "I/O2_3") (pintype "bidirectional"))
      (node (ref "R102") (pin "2") (pinfunction "E_2") (pintype "passive"))
      (node (ref "R54") (pin "1") (pinfunction "A_1") (pintype "passive"))
    )
    (net (code "15") (name "Net-(IC1-I{slash}O3)") (class "Default")
      (node (ref "C6") (pin "1") (pinfunction "1_1") (pintype "passive"))
      (node (ref "IC1") (pin "4") (pinfunction "I/O3_4") (pintype "bidirectional"))
      (node (ref "R103") (pin "2") (pinfunction "E_2") (pintype "passive"))
      (node (ref "R55") (pin "1") (pinfunction "A_1") (pintype "passive"))
    )
    (net (code "16") (name "Net-(IC1-I{slash}O4)") (class "Default")
      (node (ref "C7") (pin "1") (pinfunction "1_1") (pintype "passive"))
      (node (ref "IC1") (pin "6") (pinfunction "I/O4_6") (pintype "bidirectional"))
      (node (ref "R104") (pin "2") (pinfunction "E_2") (pintype "passive"))
      (node (ref "R56") (pin "1") (pinfunction "A_1") (pintype "passive"))
    )
    (net (code "17") (name "Net-(IC2-I{slash}O1)") (class "Default")
      (node (ref "C8") (pin "1") (pinfunction "1_1") (pintype "passive"))
      (node (ref "IC2") (pin "1") (pinfunction "I/O1_1") (pintype "bidirectional"))
      (node (ref "R105") (pin "2") (pinfunction "E_2") (pintype "passive"))
      (node (ref "R57") (pin "1") (pinfunction "A_1") (pintype "passive"))
    )
    (net (code "18") (name "Net-(IC2-I{slash}O2)") (class "Default")
      (node (ref "C9") (pin "1") (pinfunction "1_1") (pintype "passive"))
      (node (ref "IC2") (pin "3") (pinfunction "I/O2_3") (pintype "bidirectional"))
      (node (ref "R106") (pin "2") (pinfunction "E_2") (pintype "passive"))
      (node (ref "R58") (pin "1") (pinfunction "A_1") (pintype "passive"))
    )
    (net (code "19") (name "Net-(IC2-I{slash}O3)") (class "Default")
      (node (ref "C10") (pin "1") (pinfunction "1_1") (pintype "passive"))
      (node (ref "IC2") (pin "4") (pinfunction "I/O3_4") (pintype "bidirectional"))
      (node (ref "R107") (pin "2") (pinfunction "E_2") (pintype "passive"))
      (node (ref "R59") (pin "1") (pinfunction "A_1") (pintype "passive"))
    )
    (net (code "20") (name "Net-(IC2-I{slash}O4)") (class "Default")
      (node (ref "C11") (pin "1") (pinfunction "1_1") (pintype "passive"))
      (node (ref "IC2") (pin "6") (pinfunction "I/O4_6") (pintype "bidirectional"))
      (node (ref "R108") (pin "2") (pinfunction "E_2") (pintype "passive"))
      (node (ref "R60") (pin "1") (pinfunction "A_1") (pintype "passive"))
    )
    (net (code "21") (name "Net-(IC3-I{slash}O1)") (class "Default")
      (node (ref "C12") (pin "1") (pinfunction "1_1") (pintype "passive"))
      (node (ref "IC3") (pin "1") (pinfunction "I/O1_1") (pintype "bidirectional"))
      (node (ref "R109") (pin "2") (pinfunction "E_2") (pintype "passive"))
      (node (ref "R61") (pin "1") (pinfunction "A_1") (pintype "passive"))
    )
    (net (code "22") (name "Net-(IC3-I{slash}O2)") (class "Default")
      (node (ref "C13") (pin "1") (pinfunction "1_1") (pintype "passive"))
      (node (ref "IC3") (pin "3") (pinfunction "I/O2_3") (pintype "bidirectional"))
      (node (ref "R110") (pin "2") (pinfunction "E_2") (pintype "passive"))
      (node (ref "R62") (pin "1") (pinfunction "A_1") (pintype "passive"))
    )
    (net (code "23") (name "Net-(IC3-I{slash}O3)") (class "Default")
      (node (ref "C14") (pin "1") (pinfunction "1_1") (pintype "passive"))
      (node (ref "IC3") (pin "4") (pinfunction "I/O3_4") (pintype "bidirectional"))
      (node (ref "R111") (pin "2") (pinfunction "E_2") (pintype "passive"))
      (node (ref "R63") (pin "1") (pinfunction "A_1") (pintype "passive"))
    )
    (net (code "24") (name "Net-(IC3-I{slash}O4)") (class "Default")
      (node (ref "C15") (pin "1") (pinfunction "1_1") (pintype "passive"))
      (node (ref "IC3") (pin "6") (pinfunction "I/O4_6") (pintype "bidirectional"))
      (node (ref "R112") (pin "2") (pinfunction "E_2") (pintype "passive"))
      (node (ref "R64") (pin "1") (pinfunction "A_1") (pintype "passive"))
    )
    (net (code "25") (name "Net-(IC4-I{slash}O1)") (class "Default")
      (node (ref "C16") (pin "1") (pinfunction "1_1") (pintype "passive"))
      (node (ref "IC4") (pin "1") (pinfunction "I/O1_1") (pintype "bidirectional"))
      (node (ref "R113") (pin "2") (pinfunction "E_2") (pintype "passive"))
      (node (ref "R65") (pin "1") (pinfunction "A_1") (pintype "passive"))
    )
    (net (code "26") (name "Net-(IC4-I{slash}O2)") (class "Default")
      (node (ref "C17") (pin "1") (pinfunction "1_1") (pintype "passive"))
      (node (ref "IC4") (pin "3") (pinfunction "I/O2_3") (pintype "bidirectional"))
      (node (ref "R114") (pin "2") (pinfunction "E_2") (pintype "passive"))
      (node (ref "R66") (pin "1") (pinfunction "A_1") (pintype "passive"))
    )
    (net (code "27") (name "Net-(IC4-I{slash}O3)") (class "Default")
      (node (ref "C18") (pin "1") (pinfunction "1_1") (pintype "passive"))
      (node (ref "IC4") (pin "4") (pinfunction "I/O3_4") (pintype "bidirectional"))
      (node (ref "R115") (pin "2") (pinfunction "E_2") (pintype "passive"))
      (node (ref "R67") (pin "1") (pinfunction "A_1") (pintype "passive"))
    )
    (net (code "28") (name "Net-(IC4-I{slash}O4)") (class "Default")
      (node (ref "C19") (pin "1") (pinfunction "1_1") (pintype "passive"))
      (node (ref "IC4") (pin "6") (pinfunction "I/O4_6") (pintype "bidirectional"))
      (node (ref "R116") (pin "2") (pinfunction "E_2") (pintype "passive"))
      (node (ref "R68") (pin "1") (pinfunction "A_1") (pintype "passive"))
    )
    (net (code "29") (name "Net-(IC5-I{slash}O1)") (class "Default")
      (node (ref "C20") (pin "1") (pinfunction "1_1") (pintype "passive"))
      (node (ref "IC5") (pin "1") (pinfunction "I/O1_1") (pintype "bidirectional"))
      (node (ref "R117") (pin "2") (pinfunction "E_2") (pintype "passive"))
      (node (ref "R69") (pin "1") (pinfunction "A_1") (pintype "passive"))
    )
    (net (code "30") (name "Net-(IC5-I{slash}O2)") (class "Default")
      (node (ref "C21") (pin "1") (pinfunction "1_1") (pintype "passive"))
      (node (ref "IC5") (pin "3") (pinfunction "I/O2_3") (pintype "bidirectional"))
      (node (ref "R118") (pin "2") (pinfunction "E_2") (pintype "passive"))
      (node (ref "R70") (pin "1") (pinfunction "A_1") (pintype "passive"))
    )
    (net (code "31") (name "Net-(IC5-I{slash}O3)") (class "Default")
      (node (ref "C22") (pin "1") (pinfunction "1_1") (pintype "passive"))
      (node (ref "IC5") (pin "4") (pinfunction "I/O3_4") (pintype "bidirectional"))
      (node (ref "R119") (pin "2") (pinfunction "E_2") (pintype "passive"))
      (node (ref "R71") (pin "1") (pinfunction "A_1") (pintype "passive"))
    )
    (net (code "32") (name "Net-(IC5-I{slash}O4)") (class "Default")
      (node (ref "C23") (pin "1") (pinfunction "1_1") (pintype "passive"))
      (node (ref "IC5") (pin "6") (pinfunction "I/O4_6") (pintype "bidirectional"))
      (node (ref "R120") (pin "2") (pinfunction "E_2") (pintype "passive"))
      (node (ref "R72") (pin "1") (pinfunction "A_1") (pintype "passive"))
    )
    (net (code "33") (name "Net-(IC6-I{slash}O1)") (class "Default")
      (node (ref "C24") (pin "1") (pinfunction "1_1") (pintype "passive"))
      (node (ref "IC6") (pin "1") (pinfunction "I/O1_1") (pintype "bidirectional"))
      (node (ref "R121") (pin "2") (pinfunction "E_2") (pintype "passive"))
      (node (ref "R73") (pin "1") (pinfunction "A_1") (pintype "passive"))
    )
    (net (code "34") (name "Net-(IC6-I{slash}O2)") (class "Default")
      (node (ref "C25") (pin "1") (pinfunction "1_1") (pintype "passive"))
      (node (ref "IC6") (pin "3") (pinfunction "I/O2_3") (pintype "bidirectional"))
      (node (ref "R122") (pin "2") (pinfunction "E_2") (pintype "passive"))
      (node (ref "R74") (pin "1") (pinfunction "A_1") (pintype "passive"))
    )
    (net (code "35") (name "Net-(IC6-I{slash}O3)") (class "Default")
      (node (ref "C26") (pin "1") (pinfunction "1_1") (pintype "passive"))
      (node (ref "IC6") (pin "4") (pinfunction "I/O3_4") (pintype "bidirectional"))
      (node (ref "R123") (pin "2") (pinfunction "E_2") (pintype "passive"))
      (node (ref "R75") (pin "1") (pinfunction "A_1") (pintype "passive"))
    )
    (net (code "36") (name "Net-(IC6-I{slash}O4)") (class "Default")
      (node (ref "C27") (pin "1") (pinfunction "1_1") (pintype "passive"))
      (node (ref "IC6") (pin "6") (pinfunction "I/O4_6") (pintype "bidirectional"))
      (node (ref "R124") (pin "2") (pinfunction "E_2") (pintype "passive"))
      (node (ref "R76") (pin "1") (pinfunction "A_1") (pintype "passive"))
    )
    (net (code "37") (name "Net-(IC7-02_SDI)") (class "Default")
      (node (ref "IC7") (pin "2") (pinfunction "02_SDI_2") (pintype "input"))
      (node (ref "PIC1") (pin "43") (pinfunction "RC5/SDO_43") (pintype "bidirectional"))
    )
    (net (code "38") (name "Net-(IC7-03_CLK)") (class "Default")
      (node (ref "IC7") (pin "3") (pinfunction "03_CLK_3") (pintype "input"))
      (node (ref "IC8") (pin "3") (pinfunction "03_CLK_3") (pintype "input"))
      (node (ref "IC9") (pin "3") (pinfunction "03_CLK_3") (pintype "input"))
      (node (ref "PIC1") (pin "37") (pinfunction "RC3/SCK/SCL_37") (pintype "bidirectional"))
    )
    (net (code "39") (name "Net-(IC7-04_~{LA})") (class "Default")
      (node (ref "IC7") (pin "4") (pinfunction "04_~{LA}_4") (pintype "input"))
      (node (ref "IC8") (pin "4") (pinfunction "04_~{LA}_4") (pintype "input"))
      (node (ref "IC9") (pin "4") (pinfunction "04_~{LA}_4") (pintype "input"))
      (node (ref "PIC1") (pin "36") (pinfunction "RC2/CCP1_36") (pintype "bidirectional"))
    )
    (net (code "40") (name "Net-(IC7-05_OUT0)") (class "Default")
      (node (ref "IC7") (pin "5") (pinfunction "05_OUT0_5") (pintype "output"))
      (node (ref "R5") (pin "2") (pinfunction "E_2") (pintype "passive"))
      (node (ref "TR5") (pin "P$1") (pinfunction "G_P$1") (pintype "passive"))
    )
    (net (code "41") (name "Net-(IC7-06_OUT1)") (class "Default")
      (node (ref "IC7") (pin "6") (pinfunction "06_OUT1_6") (pintype "output"))
      (node (ref "R6") (pin "2") (pinfunction "E_2") (pintype "passive"))
      (node (ref "TR5") (pin "P$3") (pinfunction "G_P$3") (pintype "passive"))
    )
    (net (code "42") (name "Net-(IC7-07_OUT2)") (class "Default")
      (node (ref "IC7") (pin "7") (pinfunction "07_OUT2_7") (pintype "output"))
      (node (ref "R7") (pin "2") (pinfunction "E_2") (pintype "passive"))
      (node (ref "TR6") (pin "P$1") (pinfunction "G_P$1") (pintype "passive"))
    )
    (net (code "43") (name "Net-(IC7-08_OUT3)") (class "Default")
      (node (ref "IC7") (pin "8") (pinfunction "08_OUT3_8") (pintype "output"))
      (node (ref "R8") (pin "2") (pinfunction "E_2") (pintype "passive"))
      (node (ref "TR6") (pin "P$3") (pinfunction "G_P$3") (pintype "passive"))
    )
    (net (code "44") (name "Net-(IC7-09_OUT4)") (class "Default")
      (node (ref "IC7") (pin "9") (pinfunction "09_OUT4_9") (pintype "output"))
      (node (ref "R9") (pin "2") (pinfunction "E_2") (pintype "passive"))
      (node (ref "TR7") (pin "P$1") (pinfunction "G_P$1") (pintype "passive"))
    )
    (net (code "45") (name "Net-(IC7-10_OUT5)") (class "Default")
      (node (ref "IC7") (pin "10") (pinfunction "10_OUT5_10") (pintype "output"))
      (node (ref "R10") (pin "2") (pinfunction "E_2") (pintype "passive"))
      (node (ref "TR7") (pin "P$3") (pinfunction "G_P$3") (pintype "passive"))
    )
    (net (code "46") (name "Net-(IC7-11_OUT6)") (class "Default")
      (node (ref "IC7") (pin "11") (pinfunction "11_OUT6_11") (pintype "output"))
      (node (ref "R11") (pin "2") (pinfunction "E_2") (pintype "passive"))
      (node (ref "TR") (pin "P$1") (pinfunction "G_P$1") (pintype "passive"))
    )
    (net (code "47") (name "Net-(IC7-12_OUT7)") (class "Default")
      (node (ref "IC7") (pin "12") (pinfunction "12_OUT7_12") (pintype "output"))
      (node (ref "R12") (pin "2") (pinfunction "E_2") (pintype "passive"))
      (node (ref "TR") (pin "P$3") (pinfunction "G_P$3") (pintype "passive"))
    )
    (net (code "48") (name "Net-(IC7-14_SDO)") (class "Default")
      (node (ref "IC7") (pin "14") (pinfunction "14_SDO_14") (pintype "output"))
      (node (ref "IC8") (pin "2") (pinfunction "02_SDI_2") (pintype "input"))
    )
    (net (code "49") (name "Net-(IC7-15_REXT)") (class "Default")
      (node (ref "IC7") (pin "15") (pinfunction "15_REXT_15") (pintype "bidirectional"))
      (node (ref "R2") (pin "2") (pinfunction "E_2") (pintype "passive"))
    )
    (net (code "50") (name "Net-(IC8-05_OUT0)") (class "Default")
      (node (ref "IC8") (pin "5") (pinfunction "05_OUT0_5") (pintype "output"))
      (node (ref "R13") (pin "2") (pinfunction "E_2") (pintype "passive"))
      (node (ref "TR9") (pin "P$1") (pinfunction "G_P$1") (pintype "passive"))
    )
    (net (code "51") (name "Net-(IC8-06_OUT1)") (class "Default")
      (node (ref "IC8") (pin "6") (pinfunction "06_OUT1_6") (pintype "output"))
      (node (ref "R14") (pin "2") (pinfunction "E_2") (pintype "passive"))
      (node (ref "TR9") (pin "P$3") (pinfunction "G_P$3") (pintype "passive"))
    )
    (net (code "52") (name "Net-(IC8-07_OUT2)") (class "Default")
      (node (ref "IC8") (pin "7") (pinfunction "07_OUT2_7") (pintype "output"))
      (node (ref "R15") (pin "2") (pinfunction "E_2") (pintype "passive"))
      (node (ref "TR10") (pin "P$1") (pinfunction "G_P$1") (pintype "passive"))
    )
    (net (code "53") (name "Net-(IC8-08_OUT3)") (class "Default")
      (node (ref "IC8") (pin "8") (pinfunction "08_OUT3_8") (pintype "output"))
      (node (ref "R16") (pin "2") (pinfunction "E_2") (pintype "passive"))
      (node (ref "TR10") (pin "P$3") (pinfunction "G_P$3") (pintype "passive"))
    )
    (net (code "54") (name "Net-(IC8-09_OUT4)") (class "Default")
      (node (ref "IC8") (pin "9") (pinfunction "09_OUT4_9") (pintype "output"))
      (node (ref "R17") (pin "2") (pinfunction "E_2") (pintype "passive"))
      (node (ref "TR11") (pin "P$1") (pinfunction "G_P$1") (pintype "passive"))
    )
    (net (code "55") (name "Net-(IC8-10_OUT5)") (class "Default")
      (node (ref "IC8") (pin "10") (pinfunction "10_OUT5_10") (pintype "output"))
      (node (ref "R18") (pin "2") (pinfunction "E_2") (pintype "passive"))
      (node (ref "TR11") (pin "P$3") (pinfunction "G_P$3") (pintype "passive"))
    )
    (net (code "56") (name "Net-(IC8-11_OUT6)") (class "Default")
      (node (ref "IC8") (pin "11") (pinfunction "11_OUT6_11") (pintype "output"))
      (node (ref "R19") (pin "2") (pinfunction "E_2") (pintype "passive"))
      (node (ref "TR12") (pin "P$1") (pinfunction "G_P$1") (pintype "passive"))
    )
    (net (code "57") (name "Net-(IC8-12_OUT7)") (class "Default")
      (node (ref "IC8") (pin "12") (pinfunction "12_OUT7_12") (pintype "output"))
      (node (ref "R20") (pin "2") (pinfunction "E_2") (pintype "passive"))
      (node (ref "TR12") (pin "P$3") (pinfunction "G_P$3") (pintype "passive"))
    )
    (net (code "58") (name "Net-(IC8-14_SDO)") (class "Default")
      (node (ref "IC8") (pin "14") (pinfunction "14_SDO_14") (pintype "output"))
      (node (ref "IC9") (pin "2") (pinfunction "02_SDI_2") (pintype "input"))
    )
    (net (code "59") (name "Net-(IC8-15_REXT)") (class "Default")
      (node (ref "IC8") (pin "15") (pinfunction "15_REXT_15") (pintype "bidirectional"))
      (node (ref "R3") (pin "2") (pinfunction "E_2") (pintype "passive"))
    )
    (net (code "60") (name "Net-(IC9-05_OUT0)") (class "Default")
      (node (ref "IC9") (pin "5") (pinfunction "05_OUT0_5") (pintype "output"))
      (node (ref "R21") (pin "2") (pinfunction "E_2") (pintype "passive"))
      (node (ref "TR13") (pin "P$1") (pinfunction "G_P$1") (pintype "passive"))
    )
    (net (code "61") (name "Net-(IC9-06_OUT1)") (class "Default")
      (node (ref "IC9") (pin "6") (pinfunction "06_OUT1_6") (pintype "output"))
      (node (ref "R22") (pin "2") (pinfunction "E_2") (pintype "passive"))
      (node (ref "TR13") (pin "P$3") (pinfunction "G_P$3") (pintype "passive"))
    )
    (net (code "62") (name "Net-(IC9-07_OUT2)") (class "Default")
      (node (ref "IC9") (pin "7") (pinfunction "07_OUT2_7") (pintype "output"))
      (node (ref "R23") (pin "2") (pinfunction "E_2") (pintype "passive"))
      (node (ref "TR14") (pin "P$1") (pinfunction "G_P$1") (pintype "passive"))
    )
    (net (code "63") (name "Net-(IC9-08_OUT3)") (class "Default")
      (node (ref "IC9") (pin "8") (pinfunction "08_OUT3_8") (pintype "output"))
      (node (ref "R24") (pin "2") (pinfunction "E_2") (pintype "passive"))
      (node (ref "TR14") (pin "P$3") (pinfunction "G_P$3") (pintype "passive"))
    )
    (net (code "64") (name "Net-(IC9-09_OUT4)") (class "Default")
      (node (ref "IC9") (pin "9") (pinfunction "09_OUT4_9") (pintype "output"))
      (node (ref "R25") (pin "2") (pinfunction "E_2") (pintype "passive"))
      (node (ref "TR15") (pin "P$1") (pinfunction "G_P$1") (pintype "passive"))
    )
    (net (code "65") (name "Net-(IC9-10_OUT5)") (class "Default")
      (node (ref "IC9") (pin "10") (pinfunction "10_OUT5_10") (pintype "output"))
      (node (ref "R26") (pin "2") (pinfunction "E_2") (pintype "passive"))
      (node (ref "TR15") (pin "P$3") (pinfunction "G_P$3") (pintype "passive"))
    )
    (net (code "66") (name "Net-(IC9-11_OUT6)") (class "Default")
      (node (ref "IC9") (pin "11") (pinfunction "11_OUT6_11") (pintype "output"))
      (node (ref "R27") (pin "2") (pinfunction "E_2") (pintype "passive"))
      (node (ref "TR16") (pin "P$1") (pinfunction "G_P$1") (pintype "passive"))
    )
    (net (code "67") (name "Net-(IC9-12_OUT7)") (class "Default")
      (node (ref "IC9") (pin "12") (pinfunction "12_OUT7_12") (pintype "output"))
      (node (ref "R28") (pin "2") (pinfunction "E_2") (pintype "passive"))
      (node (ref "TR16") (pin "P$3") (pinfunction "G_P$3") (pintype "passive"))
    )
    (net (code "68") (name "Net-(IC9-15_REXT)") (class "Default")
      (node (ref "IC9") (pin "15") (pinfunction "15_REXT_15") (pintype "bidirectional"))
      (node (ref "R4") (pin "2") (pinfunction "E_2") (pintype "passive"))
    )
    (net (code "69") (name "Net-(PIC1-OSC1{slash}CLKI{slash}RA7)") (class "Default")
      (node (ref "C2") (pin "1") (pinfunction "1_1") (pintype "passive"))
      (node (ref "PIC1") (pin "30") (pinfunction "OSC1/CLKI/RA7_30") (pintype "bidirectional"))
      (node (ref "XT1") (pin "3") (pinfunction "3_3") (pintype "passive"))
    )
    (net (code "70") (name "Net-(PIC1-OSC2{slash}CLKO{slash}RA6)") (class "Default")
      (node (ref "C1") (pin "1") (pinfunction "1_1") (pintype "passive"))
      (node (ref "PIC1") (pin "31") (pinfunction "OSC2/CLKO/RA6_31") (pintype "bidirectional"))
      (node (ref "XT1") (pin "1") (pinfunction "1_1") (pintype "passive"))
    )
    (net (code "71") (name "Net-(PIC1-RA0{slash}AN0{slash}CVREF)") (class "Default")
      (node (ref "PIC1") (pin "19") (pinfunction "RA0/AN0/CVREF_19") (pintype "bidirectional"))
      (node (ref "R112") (pin "1") (pinfunction "A_1") (pintype "passive"))
    )
    (net (code "72") (name "Net-(PIC1-RA1{slash}AN1)") (class "Default")
      (node (ref "PIC1") (pin "20") (pinfunction "RA1/AN1_20") (pintype "bidirectional"))
      (node (ref "R113") (pin "1") (pinfunction "A_1") (pintype "passive"))
    )
    (net (code "73") (name "Net-(PIC1-RA2{slash}AN2{slash}VREF-)") (class "Default")
      (node (ref "PIC1") (pin "21") (pinfunction "RA2/AN2/VREF-_21") (pintype "bidirectional"))
      (node (ref "R107") (pin "1") (pinfunction "A_1") (pintype "passive"))
    )
    (net (code "74") (name "Net-(PIC1-RA3{slash}AN3{slash}VREF+)") (class "Default")
      (node (ref "PIC1") (pin "22") (pinfunction "RA3/AN3/VREF+_22") (pintype "bidirectional"))
      (node (ref "R116") (pin "1") (pinfunction "A_1") (pintype "passive"))
    )
    (net (code "75") (name "Net-(PIC1-RA5{slash}AN4{slash}~{SS{slash}HLVDIN})") (class "Default")
      (node (ref "PIC1") (pin "24") (pinfunction "RA5/AN4/~{SS/HLVDIN}_24") (pintype "bidirectional"))
      (node (ref "R108") (pin "1") (pinfunction "A_1") (pintype "passive"))
    )
    (net (code "76") (name "Net-(PIC1-RB0{slash}INT0{slash}FLT0{slash}AN10)") (class "Default")
      (node (ref "PIC1") (pin "8") (pinfunction "RB0/INT0/FLT0/AN10_8") (pintype "bidirectional"))
      (node (ref "R122") (pin "1") (pinfunction "A_1") (pintype "passive"))
    )
    (net (code "77") (name "Net-(PIC1-RB1{slash}INT1{slash}AN8)") (class "Default")
      (node (ref "PIC1") (pin "9") (pinfunction "RB1/INT1/AN8_9") (pintype "bidirectional"))
      (node (ref "R123") (pin "1") (pinfunction "A_1") (pintype "passive"))
    )
    (net (code "78") (name "Net-(PIC1-RB4{slash}KBI0{slash}AN9)") (class "Default")
      (node (ref "PIC1") (pin "14") (pinfunction "RB4/KBI0/AN9_14") (pintype "bidirectional"))
      (node (ref "R124") (pin "1") (pinfunction "A_1") (pintype "passive"))
    )
    (net (code "79") (name "Net-(PIC1-RB5{slash}KBI1{slash}PGM)") (class "Default")
      (node (ref "PIC1") (pin "15") (pinfunction "RB5/KBI1/PGM_15") (pintype "bidirectional"))
      (node (ref "R109") (pin "1") (pinfunction "A_1") (pintype "passive"))
    )
    (net (code "80") (name "Net-(PIC1-RB6{slash}KBI2{slash}PGC)") (class "Default")
      (node (ref "CN3") (pin "5") (pinfunction "5_5") (pintype "passive"))
      (node (ref "CN3") (pin "6") (pinfunction "6_6") (pintype "passive"))
      (node (ref "CN_TANIT") (pin "5") (pinfunction "5_5") (pintype "passive"))
      (node (ref "PIC1") (pin "16") (pinfunction "RB6/KBI2/PGC_16") (pintype "bidirectional"))
    )
    (net (code "81") (name "Net-(PIC1-RB7{slash}KBI3{slash}PGD)") (class "Default")
      (node (ref "CN3") (pin "7") (pinfunction "7_7") (pintype "passive"))
      (node (ref "CN3") (pin "8") (pinfunction "8_8") (pintype "passive"))
      (node (ref "CN_TANIT") (pin "4") (pinfunction "4_4") (pintype "passive"))
      (node (ref "PIC1") (pin "17") (pinfunction "RB7/KBI3/PGD_17") (pintype "bidirectional"))
    )
    (net (code "82") (name "Net-(PIC1-RC0{slash}T1OSO{slash}T13CKI)") (class "Default")
      (node (ref "PIC1") (pin "32") (pinfunction "RC0/T1OSO/T13CKI_32") (pintype "bidirectional"))
      (node (ref "R114") (pin "1") (pinfunction "A_1") (pintype "passive"))
    )
    (net (code "83") (name "Net-(PIC1-RC1{slash}T1OSI)") (class "Default")
      (node (ref "PIC1") (pin "35") (pinfunction "RC1/T1OSI_35") (pintype "bidirectional"))
      (node (ref "R115") (pin "1") (pinfunction "A_1") (pintype "passive"))
    )
    (net (code "84") (name "Net-(PIC1-RC4{slash}SDI{slash}SDA)") (class "Default")
      (node (ref "PIC1") (pin "42") (pinfunction "RC4/SDI/SDA_42") (pintype "bidirectional"))
      (node (ref "R102") (pin "1") (pinfunction "A_1") (pintype "passive"))
    )
    (net (code "85") (name "Net-(PIC1-RC6{slash}TX{slash}CK)") (class "Default")
      (node (ref "PIC1") (pin "44") (pinfunction "RC6/TX/CK_44") (pintype "bidirectional"))
      (node (ref "R101") (pin "1") (pinfunction "A_1") (pintype "passive"))
    )
    (net (code "86") (name "Net-(PIC1-RC7{slash}RX{slash}DT)") (class "Default")
      (node (ref "PIC1") (pin "1") (pinfunction "RC7/RX/DT_1") (pintype "bidirectional"))
      (node (ref "R117") (pin "1") (pinfunction "A_1") (pintype "passive"))
    )
    (net (code "87") (name "Net-(PIC1-RD0{slash}PSP0{slash}C1IN+)") (class "Default")
      (node (ref "PIC1") (pin "38") (pinfunction "RD0/PSP0/C1IN+_38") (pintype "bidirectional"))
      (node (ref "R104") (pin "1") (pinfunction "A_1") (pintype "passive"))
    )
    (net (code "88") (name "Net-(PIC1-RD1{slash}PSP1{slash}C1IN-)") (class "Default")
      (node (ref "PIC1") (pin "39") (pinfunction "RD1/PSP1/C1IN-_39") (pintype "bidirectional"))
      (node (ref "R103") (pin "1") (pinfunction "A_1") (pintype "passive"))
    )
    (net (code "89") (name "Net-(PIC1-RD2{slash}PSP2{slash}C2IN+)") (class "Default")
      (node (ref "PIC1") (pin "40") (pinfunction "RD2/PSP2/C2IN+_40") (pintype "bidirectional"))
      (node (ref "R111") (pin "1") (pinfunction "A_1") (pintype "passive"))
    )
    (net (code "90") (name "Net-(PIC1-RD3{slash}PSP3{slash}C2IN-)") (class "Default")
      (node (ref "PIC1") (pin "41") (pinfunction "RD3/PSP3/C2IN-_41") (pintype "bidirectional"))
      (node (ref "R110") (pin "1") (pinfunction "A_1") (pintype "passive"))
    )
    (net (code "91") (name "Net-(PIC1-RD4{slash}PSP4{slash}ECCP1{slash}P1A)") (class "Default")
      (node (ref "PIC1") (pin "2") (pinfunction "RD4/PSP4/ECCP1/P1A_2") (pintype "bidirectional"))
      (node (ref "R118") (pin "1") (pinfunction "A_1") (pintype "passive"))
    )
    (net (code "92") (name "Net-(PIC1-RD5{slash}PSP5{slash}P1B)") (class "Default")
      (node (ref "PIC1") (pin "3") (pinfunction "RD5/PSP5/P1B_3") (pintype "bidirectional"))
      (node (ref "R119") (pin "1") (pinfunction "A_1") (pintype "passive"))
    )
    (net (code "93") (name "Net-(PIC1-RD6{slash}PSP6{slash}P1C)") (class "Default")
      (node (ref "PIC1") (pin "4") (pinfunction "RD6/PSP6/P1C_4") (pintype "bidirectional"))
      (node (ref "R120") (pin "1") (pinfunction "A_1") (pintype "passive"))
    )
    (net (code "94") (name "Net-(PIC1-RD7{slash}PSP7{slash}P1D)") (class "Default")
      (node (ref "PIC1") (pin "5") (pinfunction "RD7/PSP7/P1D_5") (pintype "bidirectional"))
      (node (ref "R121") (pin "1") (pinfunction "A_1") (pintype "passive"))
    )
    (net (code "95") (name "Net-(PIC1-RE1{slash}~{WR{slash}AN6{slash}C1OUT})") (class "Default")
      (node (ref "PIC1") (pin "26") (pinfunction "RE1/~{WR/AN6/C1OUT}_26") (pintype "bidirectional"))
      (node (ref "R106") (pin "1") (pinfunction "A_1") (pintype "passive"))
    )
    (net (code "96") (name "Net-(PIC1-RE2{slash}~{CS{slash}AN7{slash}C2OUT})") (class "Default")
      (node (ref "PIC1") (pin "27") (pinfunction "RE2/~{CS/AN7/C2OUT}_27") (pintype "bidirectional"))
      (node (ref "R105") (pin "1") (pinfunction "A_1") (pintype "passive"))
    )
    (net (code "97") (name "Net-(PIC1-VDDCORE{slash}VCAP)") (class "Default")
      (node (ref "C3") (pin "1") (pinfunction "1_1") (pintype "passive"))
      (node (ref "PIC1") (pin "23") (pinfunction "VDDCORE/VCAP_23") (pintype "bidirectional"))
    )
    (net (code "98") (name "Net-(PIC1-~{MCLR{slash}VPP{slash}RE3})") (class "Default")
      (node (ref "CN_TANIT") (pin "3") (pinfunction "3_3") (pintype "passive"))
      (node (ref "PIC1") (pin "18") (pinfunction "~{MCLR/VPP/RE3}_18") (pintype "input"))
      (node (ref "R1") (pin "1") (pinfunction "A_1") (pintype "passive"))
    )
    (net (code "99") (name "Net-(R29-A)") (class "Default")
      (node (ref "R29") (pin "1") (pinfunction "A_1") (pintype "passive"))
      (node (ref "R53") (pin "2") (pinfunction "E_2") (pintype "passive"))
      (node (ref "R77") (pin "2") (pinfunction "E_2") (pintype "passive"))
      (node (ref "ZOLD_3P1") (pin "2") (pinfunction "1_2") (pintype "passive"))
    )
    (net (code "100") (name "Net-(R29-E)") (class "Default")
      (node (ref "R29") (pin "2") (pinfunction "E_2") (pintype "passive"))
      (node (ref "TR5") (pin "P$5") (pinfunction "S_P$5") (pintype "passive"))
    )
    (net (code "101") (name "Net-(R30-A)") (class "Default")
      (node (ref "R30") (pin "1") (pinfunction "A_1") (pintype "passive"))
      (node (ref "R54") (pin "2") (pinfunction "E_2") (pintype "passive"))
      (node (ref "R78") (pin "2") (pinfunction "E_2") (pintype "passive"))
      (node (ref "ZOLD_3P1") (pin "3") (pinfunction "1_3") (pintype "passive"))
    )
    (net (code "102") (name "Net-(R30-E)") (class "Default")
      (node (ref "R30") (pin "2") (pinfunction "E_2") (pintype "passive"))
      (node (ref "TR5") (pin "P$2") (pinfunction "S_P$2") (pintype "passive"))
    )
    (net (code "103") (name "Net-(R31-A)") (class "Default")
      (node (ref "R31") (pin "1") (pinfunction "A_1") (pintype "passive"))
      (node (ref "R55") (pin "2") (pinfunction "E_2") (pintype "passive"))
      (node (ref "R79") (pin "2") (pinfunction "E_2") (pintype "passive"))
      (node (ref "ZOLD_3P2") (pin "2") (pinfunction "1_2") (pintype "passive"))
    )
    (net (code "104") (name "Net-(R31-E)") (class "Default")
      (node (ref "R31") (pin "2") (pinfunction "E_2") (pintype "passive"))
      (node (ref "TR6") (pin "P$5") (pinfunction "S_P$5") (pintype "passive"))
    )
    (net (code "105") (name "Net-(R32-A)") (class "Default")
      (node (ref "R32") (pin "1") (pinfunction "A_1") (pintype "passive"))
      (node (ref "R56") (pin "2") (pinfunction "E_2") (pintype "passive"))
      (node (ref "R80") (pin "2") (pinfunction "E_2") (pintype "passive"))
      (node (ref "ZOLD_3P2") (pin "3") (pinfunction "1_3") (pintype "passive"))
    )
    (net (code "106") (name "Net-(R32-E)") (class "Default")
      (node (ref "R32") (pin "2") (pinfunction "E_2") (pintype "passive"))
      (node (ref "TR6") (pin "P$2") (pinfunction "S_P$2") (pintype "passive"))
    )
    (net (code "107") (name "Net-(R33-A)") (class "Default")
      (node (ref "R33") (pin "1") (pinfunction "A_1") (pintype "passive"))
      (node (ref "R57") (pin "2") (pinfunction "E_2") (pintype "passive"))
      (node (ref "R81") (pin "2") (pinfunction "E_2") (pintype "passive"))
      (node (ref "ZOLD_3P3") (pin "2") (pinfunction "1_2") (pintype "passive"))
    )
    (net (code "108") (name "Net-(R33-E)") (class "Default")
      (node (ref "R33") (pin "2") (pinfunction "E_2") (pintype "passive"))
      (node (ref "TR7") (pin "P$5") (pinfunction "S_P$5") (pintype "passive"))
    )
    (net (code "109") (name "Net-(R34-A)") (class "Default")
      (node (ref "R34") (pin "1") (pinfunction "A_1") (pintype "passive"))
      (node (ref "R58") (pin "2") (pinfunction "E_2") (pintype "passive"))
      (node (ref "R82") (pin "2") (pinfunction "E_2") (pintype "passive"))
      (node (ref "ZOLD_3P3") (pin "3") (pinfunction "1_3") (pintype "passive"))
    )
    (net (code "110") (name "Net-(R34-E)") (class "Default")
      (node (ref "R34") (pin "2") (pinfunction "E_2") (pintype "passive"))
      (node (ref "TR7") (pin "P$2") (pinfunction "S_P$2") (pintype "passive"))
    )
    (net (code "111") (name "Net-(R35-A)") (class "Default")
      (node (ref "R35") (pin "1") (pinfunction "A_1") (pintype "passive"))
      (node (ref "R59") (pin "2") (pinfunction "E_2") (pintype "passive"))
      (node (ref "R83") (pin "2") (pinfunction "E_2") (pintype "passive"))
      (node (ref "ZOLD_3P4") (pin "2") (pinfunction "1_2") (pintype "passive"))
    )
    (net (code "112") (name "Net-(R35-E)") (class "Default")
      (node (ref "R35") (pin "2") (pinfunction "E_2") (pintype "passive"))
      (node (ref "TR") (pin "P$5") (pinfunction "S_P$5") (pintype "passive"))
    )
    (net (code "113") (name "Net-(R36-A)") (class "Default")
      (node (ref "R36") (pin "1") (pinfunction "A_1") (pintype "passive"))
      (node (ref "R60") (pin "2") (pinfunction "E_2") (pintype "passive"))
      (node (ref "R84") (pin "2") (pinfunction "E_2") (pintype "passive"))
      (node (ref "ZOLD_3P4") (pin "3") (pinfunction "1_3") (pintype "passive"))
    )
    (net (code "114") (name "Net-(R36-E)") (class "Default")
      (node (ref "R36") (pin "2") (pinfunction "E_2") (pintype "passive"))
      (node (ref "TR") (pin "P$2") (pinfunction "S_P$2") (pintype "passive"))
    )
    (net (code "115") (name "Net-(R37-A)") (class "Default")
      (node (ref "R37") (pin "1") (pinfunction "A_1") (pintype "passive"))
      (node (ref "R61") (pin "2") (pinfunction "E_2") (pintype "passive"))
      (node (ref "R85") (pin "2") (pinfunction "E_2") (pintype "passive"))
      (node (ref "ZOLD_3P5") (pin "2") (pinfunction "1_2") (pintype "passive"))
    )
    (net (code "116") (name "Net-(R37-E)") (class "Default")
      (node (ref "R37") (pin "2") (pinfunction "E_2") (pintype "passive"))
      (node (ref "TR9") (pin "P$5") (pinfunction "S_P$5") (pintype "passive"))
    )
    (net (code "117") (name "Net-(R38-A)") (class "Default")
      (node (ref "R38") (pin "1") (pinfunction "A_1") (pintype "passive"))
      (node (ref "R62") (pin "2") (pinfunction "E_2") (pintype "passive"))
      (node (ref "R86") (pin "2") (pinfunction "E_2") (pintype "passive"))
      (node (ref "ZOLD_3P5") (pin "3") (pinfunction "1_3") (pintype "passive"))
    )
    (net (code "118") (name "Net-(R38-E)") (class "Default")
      (node (ref "R38") (pin "2") (pinfunction "E_2") (pintype "passive"))
      (node (ref "TR9") (pin "P$2") (pinfunction "S_P$2") (pintype "passive"))
    )
    (net (code "119") (name "Net-(R39-A)") (class "Default")
      (node (ref "R39") (pin "1") (pinfunction "A_1") (pintype "passive"))
      (node (ref "R63") (pin "2") (pinfunction "E_2") (pintype "passive"))
      (node (ref "R87") (pin "2") (pinfunction "E_2") (pintype "passive"))
      (node (ref "ZOLD_3P6") (pin "2") (pinfunction "1_2") (pintype "passive"))
    )
    (net (code "120") (name "Net-(R39-E)") (class "Default")
      (node (ref "R39") (pin "2") (pinfunction "E_2") (pintype "passive"))
      (node (ref "TR10") (pin "P$5") (pinfunction "S_P$5") (pintype "passive"))
    )
    (net (code "121") (name "Net-(R40-A)") (class "Default")
      (node (ref "R40") (pin "1") (pinfunction "A_1") (pintype "passive"))
      (node (ref "R64") (pin "2") (pinfunction "E_2") (pintype "passive"))
      (node (ref "R88") (pin "2") (pinfunction "E_2") (pintype "passive"))
      (node (ref "ZOLD_3P6") (pin "3") (pinfunction "1_3") (pintype "passive"))
    )
    (net (code "122") (name "Net-(R40-E)") (class "Default")
      (node (ref "R40") (pin "2") (pinfunction "E_2") (pintype "passive"))
      (node (ref "TR10") (pin "P$2") (pinfunction "S_P$2") (pintype "passive"))
    )
    (net (code "123") (name "Net-(R41-A)") (class "Default")
      (node (ref "R41") (pin "1") (pinfunction "A_1") (pintype "passive"))
      (node (ref "R65") (pin "2") (pinfunction "E_2") (pintype "passive"))
      (node (ref "R89") (pin "2") (pinfunction "E_2") (pintype "passive"))
      (node (ref "ZOLD_3P7") (pin "2") (pinfunction "1_2") (pintype "passive"))
    )
    (net (code "124") (name "Net-(R41-E)") (class "Default")
      (node (ref "R41") (pin "2") (pinfunction "E_2") (pintype "passive"))
      (node (ref "TR11") (pin "P$5") (pinfunction "S_P$5") (pintype "passive"))
    )
    (net (code "125") (name "Net-(R42-A)") (class "Default")
      (node (ref "R42") (pin "1") (pinfunction "A_1") (pintype "passive"))
      (node (ref "R66") (pin "2") (pinfunction "E_2") (pintype "passive"))
      (node (ref "R90") (pin "2") (pinfunction "E_2") (pintype "passive"))
      (node (ref "ZOLD_3P7") (pin "3") (pinfunction "1_3") (pintype "passive"))
    )
    (net (code "126") (name "Net-(R42-E)") (class "Default")
      (node (ref "R42") (pin "2") (pinfunction "E_2") (pintype "passive"))
      (node (ref "TR11") (pin "P$2") (pinfunction "S_P$2") (pintype "passive"))
    )
    (net (code "127") (name "Net-(R43-A)") (class "Default")
      (node (ref "R43") (pin "1") (pinfunction "A_1") (pintype "passive"))
      (node (ref "R67") (pin "2") (pinfunction "E_2") (pintype "passive"))
      (node (ref "R91") (pin "2") (pinfunction "E_2") (pintype "passive"))
      (node (ref "ZOLD_3P8") (pin "2") (pinfunction "1_2") (pintype "passive"))
    )
    (net (code "128") (name "Net-(R43-E)") (class "Default")
      (node (ref "R43") (pin "2") (pinfunction "E_2") (pintype "passive"))
      (node (ref "TR12") (pin "P$5") (pinfunction "S_P$5") (pintype "passive"))
    )
    (net (code "129") (name "Net-(R44-A)") (class "Default")
      (node (ref "R44") (pin "1") (pinfunction "A_1") (pintype "passive"))
      (node (ref "R68") (pin "2") (pinfunction "E_2") (pintype "passive"))
      (node (ref "R92") (pin "2") (pinfunction "E_2") (pintype "passive"))
      (node (ref "ZOLD_3P8") (pin "3") (pinfunction "1_3") (pintype "passive"))
    )
    (net (code "130") (name "Net-(R44-E)") (class "Default")
      (node (ref "R44") (pin "2") (pinfunction "E_2") (pintype "passive"))
      (node (ref "TR12") (pin "P$2") (pinfunction "S_P$2") (pintype "passive"))
    )
    (net (code "131") (name "Net-(R45-A)") (class "Default")
      (node (ref "R45") (pin "1") (pinfunction "A_1") (pintype "passive"))
      (node (ref "R69") (pin "2") (pinfunction "E_2") (pintype "passive"))
      (node (ref "R93") (pin "2") (pinfunction "E_2") (pintype "passive"))
      (node (ref "ZOLD_3P9") (pin "2") (pinfunction "1_2") (pintype "passive"))
    )
    (net (code "132") (name "Net-(R45-E)") (class "Default")
      (node (ref "R45") (pin "2") (pinfunction "E_2") (pintype "passive"))
      (node (ref "TR13") (pin "P$5") (pinfunction "S_P$5") (pintype "passive"))
    )
    (net (code "133") (name "Net-(R46-A)") (class "Default")
      (node (ref "R46") (pin "1") (pinfunction "A_1") (pintype "passive"))
      (node (ref "R70") (pin "2") (pinfunction "E_2") (pintype "passive"))
      (node (ref "R94") (pin "2") (pinfunction "E_2") (pintype "passive"))
      (node (ref "ZOLD_3P9") (pin "3") (pinfunction "1_3") (pintype "passive"))
    )
    (net (code "134") (name "Net-(R46-E)") (class "Default")
      (node (ref "R46") (pin "2") (pinfunction "E_2") (pintype "passive"))
      (node (ref "TR13") (pin "P$2") (pinfunction "S_P$2") (pintype "passive"))
    )
    (net (code "135") (name "Net-(R47-A)") (class "Default")
      (node (ref "R47") (pin "1") (pinfunction "A_1") (pintype "passive"))
      (node (ref "R71") (pin "2") (pinfunction "E_2") (pintype "passive"))
      (node (ref "R95") (pin "2") (pinfunction "E_2") (pintype "passive"))
      (node (ref "ZOLD_3P10") (pin "2") (pinfunction "1_2") (pintype "passive"))
    )
    (net (code "136") (name "Net-(R47-E)") (class "Default")
      (node (ref "R47") (pin "2") (pinfunction "E_2") (pintype "passive"))
      (node (ref "TR14") (pin "P$5") (pinfunction "S_P$5") (pintype "passive"))
    )
    (net (code "137") (name "Net-(R48-A)") (class "Default")
      (node (ref "R48") (pin "1") (pinfunction "A_1") (pintype "passive"))
      (node (ref "R72") (pin "2") (pinfunction "E_2") (pintype "passive"))
      (node (ref "R96") (pin "2") (pinfunction "E_2") (pintype "passive"))
      (node (ref "ZOLD_3P10") (pin "3") (pinfunction "1_3") (pintype "passive"))
    )
    (net (code "138") (name "Net-(R48-E)") (class "Default")
      (node (ref "R48") (pin "2") (pinfunction "E_2") (pintype "passive"))
      (node (ref "TR14") (pin "P$2") (pinfunction "S_P$2") (pintype "passive"))
    )
    (net (code "139") (name "Net-(R49-A)") (class "Default")
      (node (ref "R49") (pin "1") (pinfunction "A_1") (pintype "passive"))
      (node (ref "R73") (pin "2") (pinfunction "E_2") (pintype "passive"))
      (node (ref "R97") (pin "2") (pinfunction "E_2") (pintype "passive"))
      (node (ref "ZOLD_3P11") (pin "2") (pinfunction "1_2") (pintype "passive"))
    )
    (net (code "140") (name "Net-(R49-E)") (class "Default")
      (node (ref "R49") (pin "2") (pinfunction "E_2") (pintype "passive"))
      (node (ref "TR15") (pin "P$5") (pinfunction "S_P$5") (pintype "passive"))
    )
    (net (code "141") (name "Net-(R50-A)") (class "Default")
      (node (ref "R50") (pin "1") (pinfunction "A_1") (pintype "passive"))
      (node (ref "R74") (pin "2") (pinfunction "E_2") (pintype "passive"))
      (node (ref "R98") (pin "2") (pinfunction "E_2") (pintype "passive"))
      (node (ref "ZOLD_3P11") (pin "3") (pinfunction "1_3") (pintype "passive"))
    )
    (net (code "142") (name "Net-(R50-E)") (class "Default")
      (node (ref "R50") (pin "2") (pinfunction "E_2") (pintype "passive"))
      (node (ref "TR15") (pin "P$2") (pinfunction "S_P$2") (pintype "passive"))
    )
    (net (code "143") (name "Net-(R51-A)") (class "Default")
      (node (ref "R51") (pin "1") (pinfunction "A_1") (pintype "passive"))
      (node (ref "R75") (pin "2") (pinfunction "E_2") (pintype "passive"))
      (node (ref "R99") (pin "2") (pinfunction "E_2") (pintype "passive"))
      (node (ref "ZOLD_3P12") (pin "2") (pinfunction "1_2") (pintype "passive"))
    )
    (net (code "144") (name "Net-(R51-E)") (class "Default")
      (node (ref "R51") (pin "2") (pinfunction "E_2") (pintype "passive"))
      (node (ref "TR16") (pin "P$5") (pinfunction "S_P$5") (pintype "passive"))
    )
    (net (code "145") (name "Net-(R52-E)") (class "Default")
      (node (ref "R52") (pin "2") (pinfunction "E_2") (pintype "passive"))
      (node (ref "TR16") (pin "P$2") (pinfunction "S_P$2") (pintype "passive"))
    )
    (net (code "146") (name "Net-(R100-E)") (class "Default")
      (node (ref "R100") (pin "2") (pinfunction "E_2") (pintype "passive"))
      (node (ref "R52") (pin "1") (pinfunction "A_1") (pintype "passive"))
      (node (ref "R76") (pin "2") (pinfunction "E_2") (pintype "passive"))
      (node (ref "ZOLD_3P12") (pin "3") (pinfunction "1_3") (pintype "passive"))
    )
    (net (code "147") (name "Net-(R125-E)") (class "Default")
      (node (ref "CN_CANLEZAR") (pin "1") (pinfunction "1_1") (pintype "passive"))
      (node (ref "R125") (pin "2") (pinfunction "E_2") (pintype "passive"))
    )
    (net (code "148") (name "Net-(R126-A)") (class "Default")
      (node (ref "CN_CANLEZAR") (pin "3") (pinfunction "3_3") (pintype "passive"))
      (node (ref "R126") (pin "1") (pinfunction "A_1") (pintype "passive"))
    )
    (net (code "149") (name "unconnected-(CANIC-VREF-Pad5)") (class "Default")
      (node (ref "CANIC") (pin "5") (pinfunction "VREF_5") (pintype "output"))
    )
    (net (code "150") (name "unconnected-(CN_RJ1-Pad1)") (class "Default")
      (node (ref "CN_RJ1") (pin "1") (pinfunction "1_1") (pintype "passive"))
    )
    (net (code "151") (name "unconnected-(CN_RJ1-Pad2)") (class "Default")
      (node (ref "CN_RJ1") (pin "2") (pinfunction "2_2") (pintype "passive"))
    )
    (net (code "152") (name "unconnected-(CN_RJ1-Pad3)") (class "Default")
      (node (ref "CN_RJ1") (pin "3") (pinfunction "3_3") (pintype "passive"))
    )
    (net (code "153") (name "unconnected-(CN_RJ1-Pad6)") (class "Default")
      (node (ref "CN_RJ1") (pin "6") (pinfunction "6_6") (pintype "passive"))
    )
    (net (code "154") (name "unconnected-(CN_RJ2-Pad1)") (class "Default")
      (node (ref "CN_RJ2") (pin "1") (pinfunction "1_1") (pintype "passive"))
    )
    (net (code "155") (name "unconnected-(CN_RJ2-Pad2)") (class "Default")
      (node (ref "CN_RJ2") (pin "2") (pinfunction "2_2") (pintype "passive"))
    )
    (net (code "156") (name "unconnected-(CN_RJ2-Pad3)") (class "Default")
      (node (ref "CN_RJ2") (pin "3") (pinfunction "3_3") (pintype "passive"))
    )
    (net (code "157") (name "unconnected-(CN_RJ2-Pad6)") (class "Default")
      (node (ref "CN_RJ2") (pin "6") (pinfunction "6_6") (pintype "passive"))
    )
    (net (code "158") (name "unconnected-(IC9-14_SDO-Pad14)") (class "Default")
      (node (ref "IC9") (pin "14") (pinfunction "14_SDO_14") (pintype "output"))
    )
    (net (code "159") (name "unconnected-(PIC1-NC-Pad34)") (class "Default")
      (node (ref "PIC1") (pin "34") (pinfunction "NC_34") (pintype "no_connect"))
    )
    (net (code "160") (name "unconnected-(PIC1-NC_2-Pad12)") (class "Default")
      (node (ref "PIC1") (pin "12") (pinfunction "NC_2_12") (pintype "no_connect"))
    )
    (net (code "161") (name "unconnected-(PIC1-NC_3-Pad13)") (class "Default")
      (node (ref "PIC1") (pin "13") (pinfunction "NC_3_13") (pintype "no_connect"))
    )
    (net (code "162") (name "unconnected-(PIC1-NC_4-Pad33)") (class "Default")
      (node (ref "PIC1") (pin "33") (pinfunction "NC_4_33") (pintype "no_connect"))
    )
    (net (code "163") (name "unconnected-(PIC1-RE0{slash}~{RD{slash}AN5}-Pad25)") (class "Default")
      (node (ref "PIC1") (pin "25") (pinfunction "RE0/~{RD/AN5}_25") (pintype "bidirectional"))
    )
    (net (code "164") (name "unconnected-(U$20-PadP$2)") (class "Default")
      (node (ref "U$20") (pin "P$2") (pinfunction "P$2_P$2") (pintype "bidirectional"))
    )
  )
)
